# EEZ_DIB_DCM220_r2B8.net
KiCad netlist of a schematic drawn in EAGLE
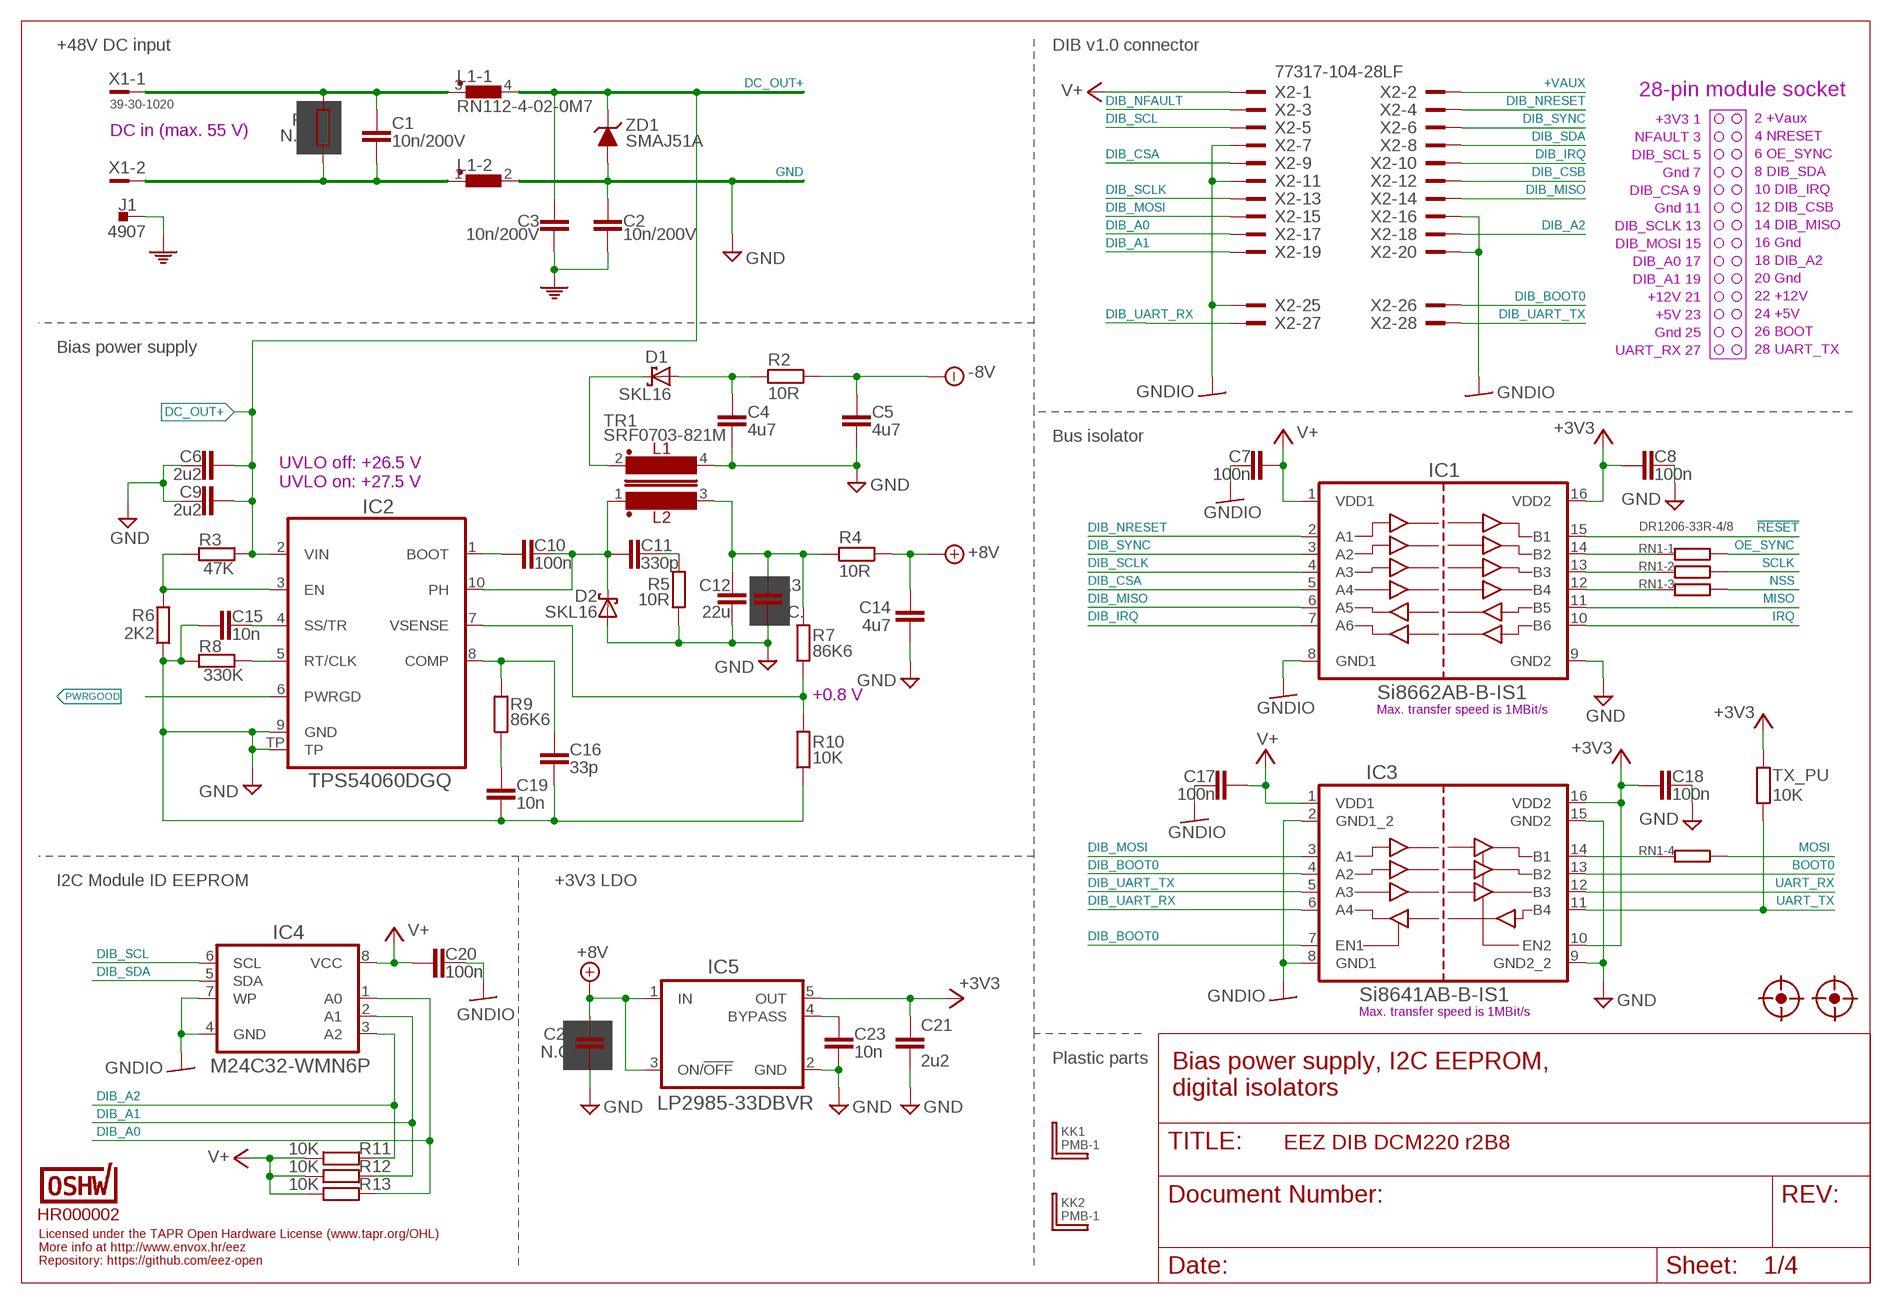
[diagram p0: schematic, sheet 1]
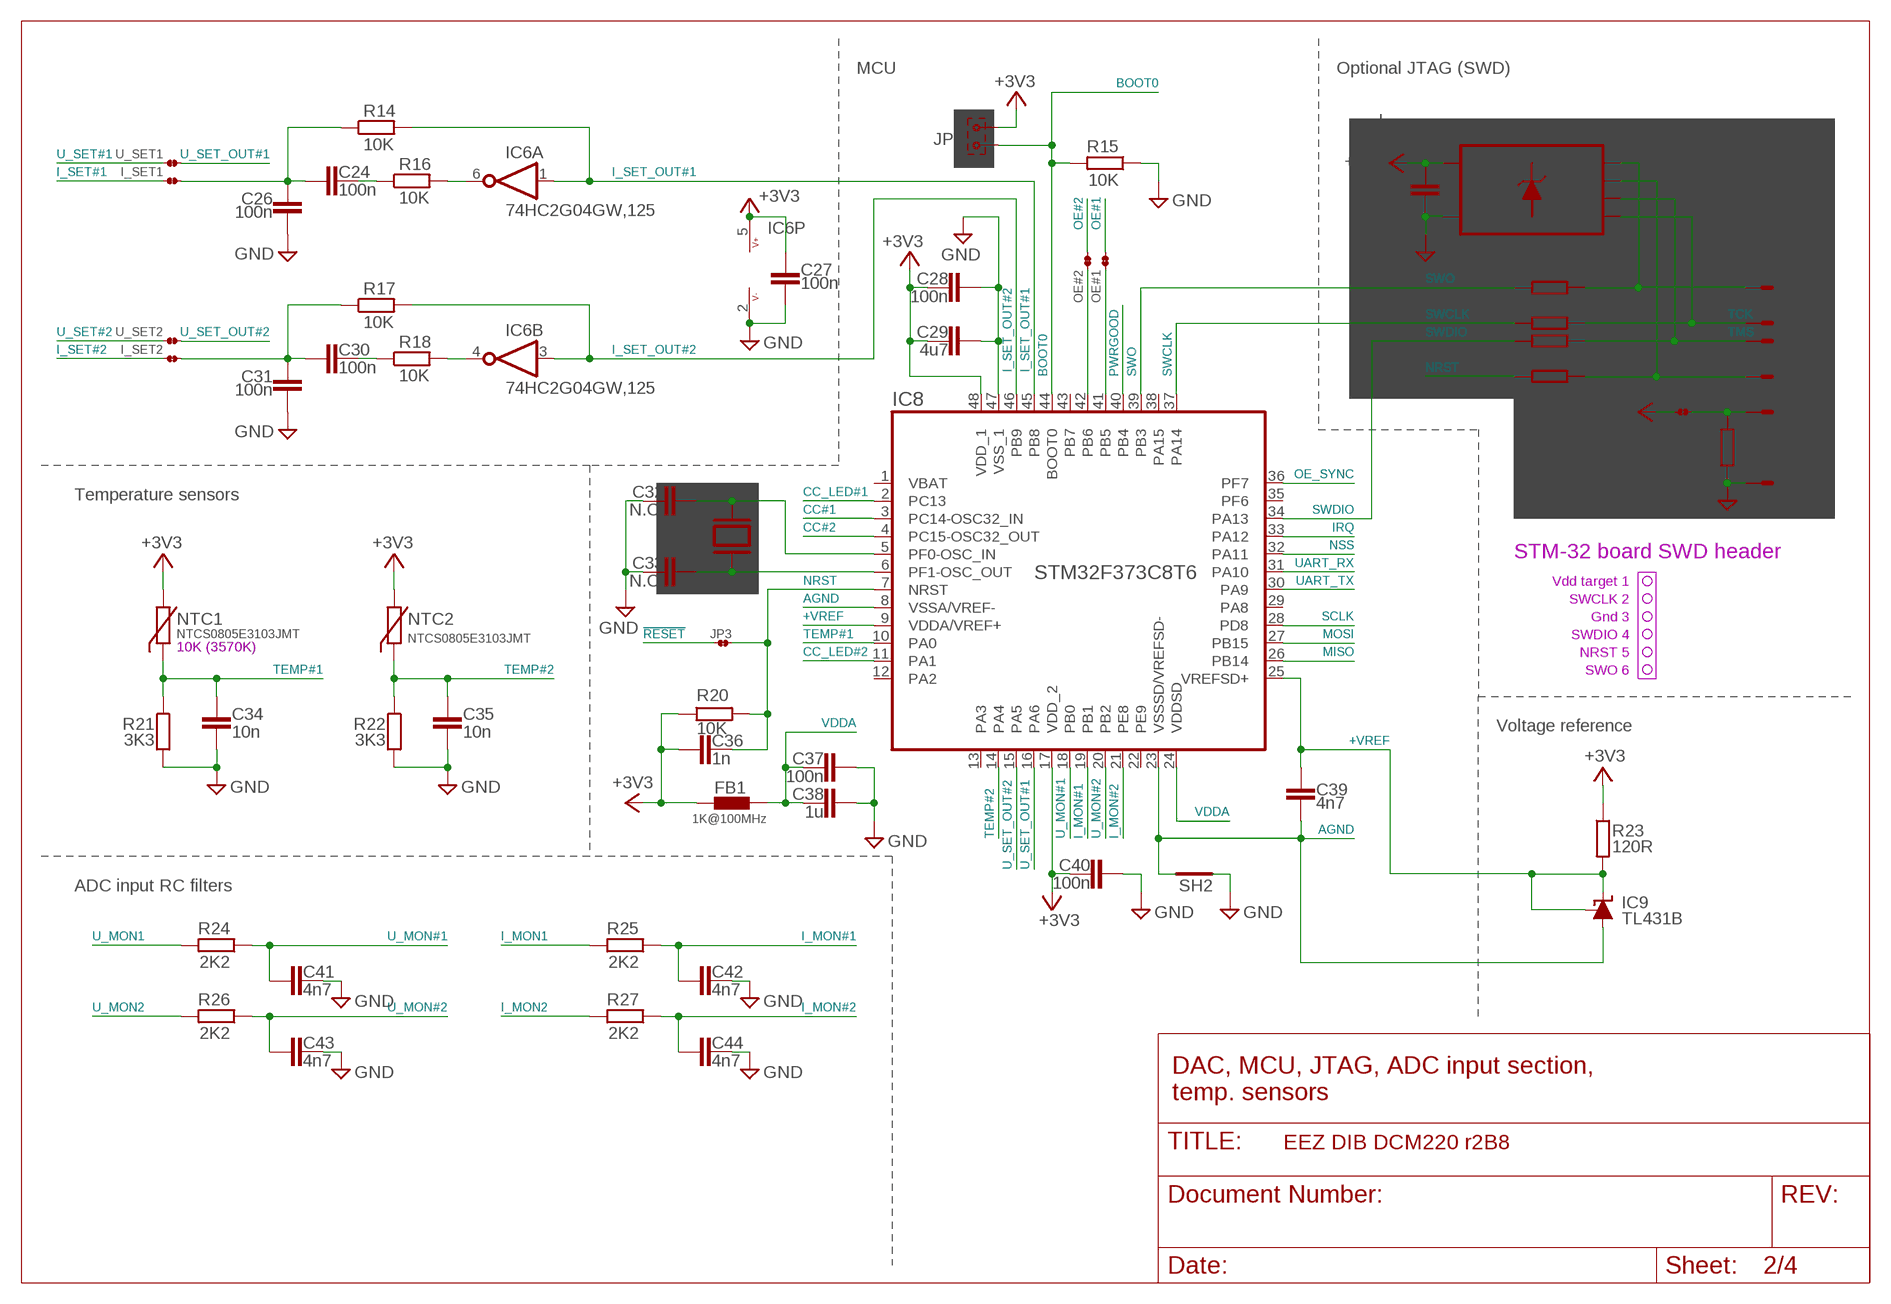
[diagram p1: schematic, sheet 2]
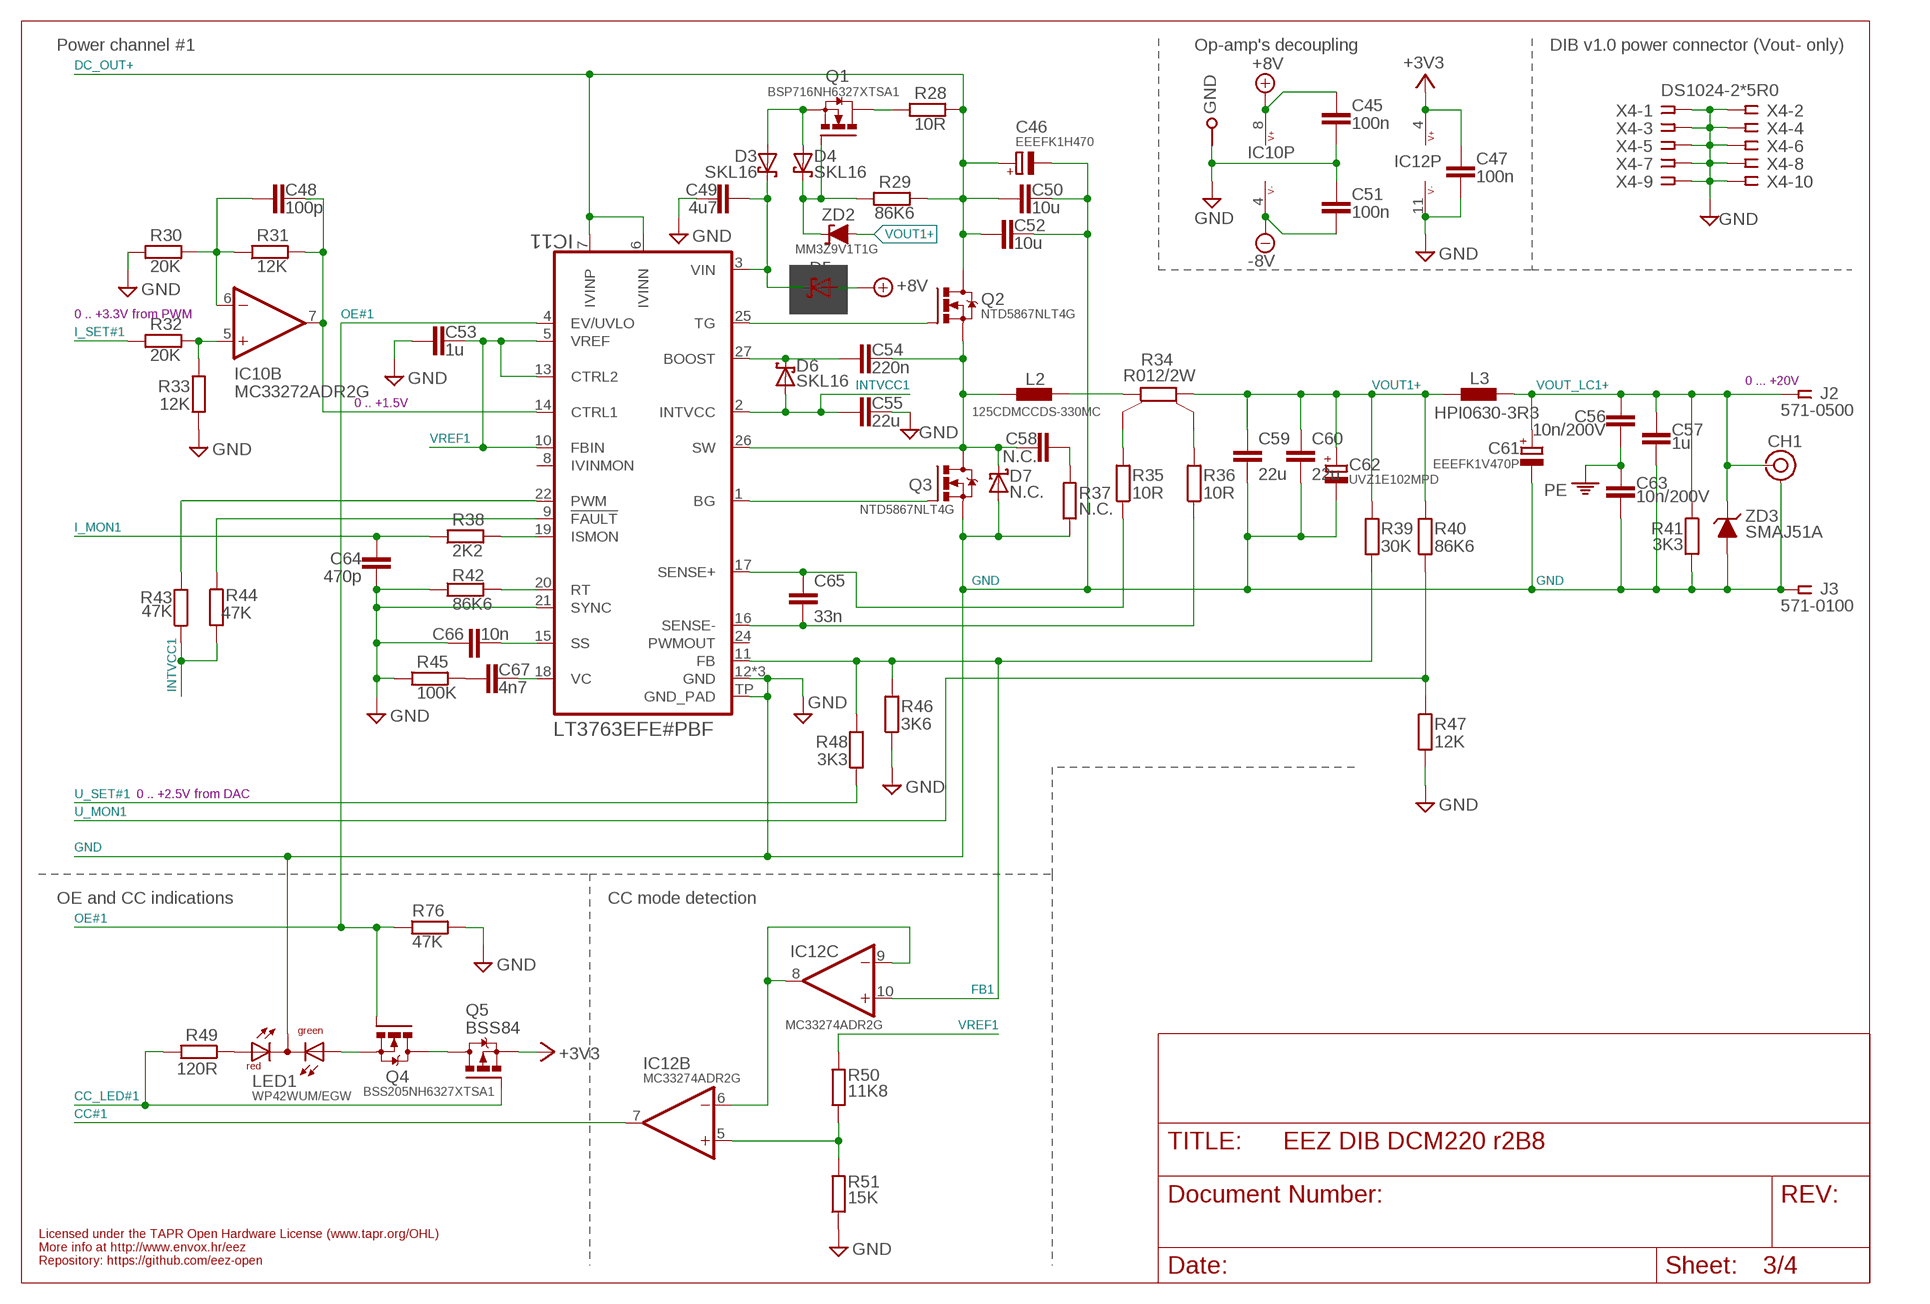
[diagram p2: schematic, sheet 3]
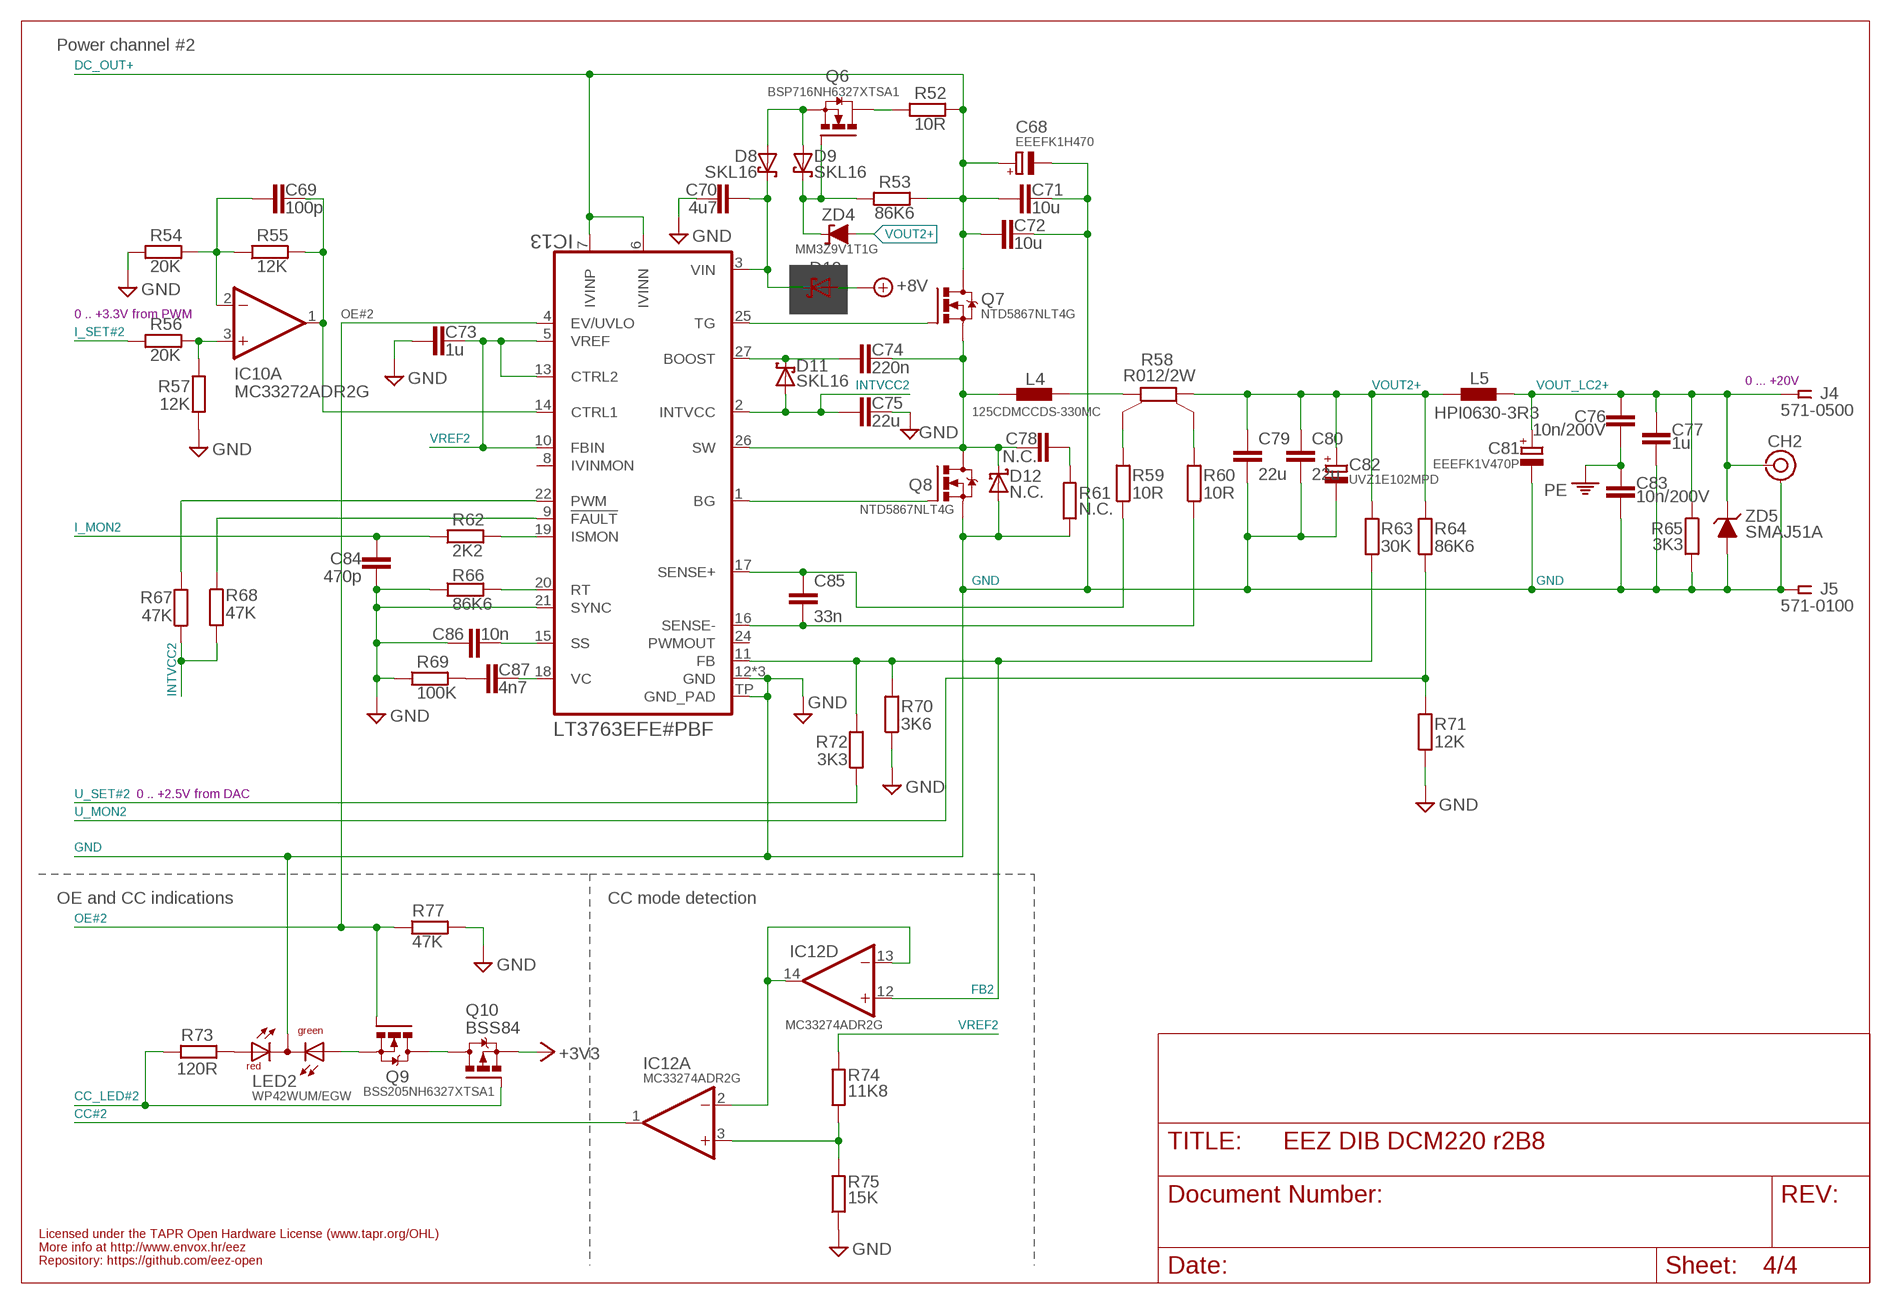
[diagram p3: schematic, sheet 4]

(export (version "E")
  (design (tool "Eeschema 10.0.6"))
  (components
    (comp (ref "C24")
      (value "100n")
      (footprint "eagle-import:C0603")
      (libsource (lib "eagle-import") (part "C-EUC0603"))
    )
    (comp (ref "C25")
      (value "N.C.")
      (footprint "eagle-import:C0603")
      (libsource (lib "eagle-import") (part "C-EUC0603"))
    )
    (comp (ref "C26")
      (value "100n")
      (footprint "eagle-import:C0603")
      (libsource (lib "eagle-import") (part "C-EUC0603"))
    )
    (comp (ref "C27")
      (value "100n")
      (footprint "eagle-import:C0603")
      (libsource (lib "eagle-import") (part "C-EUC0603"))
    )
    (comp (ref "C28")
      (value "100n")
      (footprint "eagle-import:C0603")
      (libsource (lib "eagle-import") (part "C-EUC0603"))
    )
    (comp (ref "C29")
      (value "4u7")
      (footprint "eagle-import:C1206")
      (libsource (lib "eagle-import") (part "C-EUC1206"))
    )
    (comp (ref "C30")
      (value "100n")
      (footprint "eagle-import:C0603")
      (libsource (lib "eagle-import") (part "C-EUC0603"))
    )
    (comp (ref "C31")
      (value "100n")
      (footprint "eagle-import:C0603")
      (libsource (lib "eagle-import") (part "C-EUC0603"))
    )
    (comp (ref "C32")
      (value "N.C.")
      (footprint "eagle-import:C0603")
      (libsource (lib "eagle-import") (part "C-EUC0603"))
    )
    (comp (ref "C33")
      (value "N.C.")
      (footprint "eagle-import:C0603")
      (libsource (lib "eagle-import") (part "C-EUC0603"))
    )
    (comp (ref "C34")
      (value "10n")
      (footprint "eagle-import:C0805")
      (libsource (lib "eagle-import") (part "C-EUC0805"))
    )
    (comp (ref "C35")
      (value "10n")
      (footprint "eagle-import:C0805")
      (libsource (lib "eagle-import") (part "C-EUC0805"))
    )
    (comp (ref "C36")
      (value "1n")
      (footprint "eagle-import:C0805")
      (libsource (lib "eagle-import") (part "C-EUC0805"))
    )
    (comp (ref "C37")
      (value "100n")
      (footprint "eagle-import:C0603")
      (libsource (lib "eagle-import") (part "C-EUC0603"))
    )
    (comp (ref "C38")
      (value "1u")
      (footprint "eagle-import:C0805")
      (libsource (lib "eagle-import") (part "C-EUC0805"))
    )
    (comp (ref "C39")
      (value "4n7")
      (footprint "eagle-import:C0805")
      (libsource (lib "eagle-import") (part "C-EUC0805"))
    )
    (comp (ref "C40")
      (value "100n")
      (footprint "eagle-import:C0603")
      (libsource (lib "eagle-import") (part "C-EUC0603"))
    )
    (comp (ref "C41")
      (value "4n7")
      (footprint "eagle-import:C0805")
      (libsource (lib "eagle-import") (part "C-EUC0805"))
    )
    (comp (ref "C42")
      (value "4n7")
      (footprint "eagle-import:C0805")
      (libsource (lib "eagle-import") (part "C-EUC0805"))
    )
    (comp (ref "C43")
      (value "4n7")
      (footprint "eagle-import:C0805")
      (libsource (lib "eagle-import") (part "C-EUC0805"))
    )
    (comp (ref "C44")
      (value "4n7")
      (footprint "eagle-import:C0805")
      (libsource (lib "eagle-import") (part "C-EUC0805"))
    )
    (comp (ref "FB1")
      (value "1K@100MHz")
      (footprint "eagle-import:BEAD0603")
      (libsource (lib "eagle-import") (part "FERRITE_BEAD0603"))
    )
    (comp (ref "IC6")
      (value "74HC2G04GW,125")
      (footprint "eagle-import:SOT65P210X110-6N")
      (libsource (lib "eagle-import") (part "74HC2G04"))
    )
    (comp (ref "IC7")
      (value "N.C.")
      (footprint "eagle-import:DRL6")
      (libsource (lib "eagle-import") (part "TPD4E001-DRL"))
    )
    (comp (ref "IC8")
      (value "STM32F373C8T6")
      (footprint "eagle-import:LQFP-48")
      (libsource (lib "eagle-import") (part "STM32F373C8T6"))
    )
    (comp (ref "IC9")
      (value "TL431B")
      (footprint "eagle-import:SOT103P240X110-3N")
      (libsource (lib "eagle-import") (part "TL431"))
    )
    (comp (ref "I_SET1")
      (value "JP2-NOCUT")
      (footprint "eagle-import:JP2-NOCUT")
      (libsource (lib "eagle-import") (part "JP2-NOCUT"))
    )
    (comp (ref "I_SET2")
      (value "JP2-NOCUT")
      (footprint "eagle-import:JP2-NOCUT")
      (libsource (lib "eagle-import") (part "JP2-NOCUT"))
    )
    (comp (ref "JP1")
      (value "JUMPER-2PIN-2MM")
      (footprint "eagle-import:2MM-2")
      (libsource (lib "eagle-import") (part "JUMPER-2PIN-2MM"))
    )
    (comp (ref "JP2")
      (value "JP2-CUT")
      (footprint "eagle-import:JP2-CUT")
      (libsource (lib "eagle-import") (part "JP2-CUT"))
    )
    (comp (ref "JP3")
      (value "JP2-NOCUT")
      (footprint "eagle-import:JP2-NOCUT")
      (libsource (lib "eagle-import") (part "JP2-NOCUT"))
    )
    (comp (ref "NTC1")
      (value "NTCS0805E3103JMT")
      (footprint "eagle-import:R_0805")
      (libsource (lib "eagle-import") (part "NTCR_0805"))
    )
    (comp (ref "NTC2")
      (value "NTCS0805E3103JMT")
      (footprint "eagle-import:R_0805")
      (libsource (lib "eagle-import") (part "NTCR_0805"))
    )
    (comp (ref "OE#1")
      (value "JP2-NOCUT")
      (footprint "eagle-import:JP2-NOCUT")
      (libsource (lib "eagle-import") (part "JP2-NOCUT"))
    )
    (comp (ref "OE#2")
      (value "JP2-NOCUT")
      (footprint "eagle-import:JP2-NOCUT")
      (libsource (lib "eagle-import") (part "JP2-NOCUT"))
    )
    (comp (ref "R14")
      (value "10K")
      (footprint "eagle-import:R0805")
      (libsource (lib "eagle-import") (part "R-EU_R0805"))
    )
    (comp (ref "R15")
      (value "10K")
      (footprint "eagle-import:R0805")
      (libsource (lib "eagle-import") (part "R-EU_R0805"))
    )
    (comp (ref "R16")
      (value "10K")
      (footprint "eagle-import:R0805")
      (libsource (lib "eagle-import") (part "R-EU_R0805"))
    )
    (comp (ref "R17")
      (value "10K")
      (footprint "eagle-import:R0805")
      (libsource (lib "eagle-import") (part "R-EU_R0805"))
    )
    (comp (ref "R18")
      (value "10K")
      (footprint "eagle-import:R0805")
      (libsource (lib "eagle-import") (part "R-EU_R0805"))
    )
    (comp (ref "R19")
      (value "N.C.")
      (footprint "eagle-import:R0805")
      (libsource (lib "eagle-import") (part "R-EU_R0805"))
    )
    (comp (ref "R20")
      (value "10K")
      (footprint "eagle-import:R0805")
      (libsource (lib "eagle-import") (part "R-EU_R0805"))
    )
    (comp (ref "R21")
      (value "3K3")
      (footprint "eagle-import:R0805")
      (libsource (lib "eagle-import") (part "R-EU_R0805"))
    )
    (comp (ref "R22")
      (value "3K3")
      (footprint "eagle-import:R0805")
      (libsource (lib "eagle-import") (part "R-EU_R0805"))
    )
    (comp (ref "R23")
      (value "120R")
      (footprint "eagle-import:R0805")
      (libsource (lib "eagle-import") (part "R-EU_R0805"))
    )
    (comp (ref "R24")
      (value "2K2")
      (footprint "eagle-import:R0805")
      (libsource (lib "eagle-import") (part "R-EU_R0805"))
    )
    (comp (ref "R25")
      (value "2K2")
      (footprint "eagle-import:R0805")
      (libsource (lib "eagle-import") (part "R-EU_R0805"))
    )
    (comp (ref "R26")
      (value "2K2")
      (footprint "eagle-import:R0805")
      (libsource (lib "eagle-import") (part "R-EU_R0805"))
    )
    (comp (ref "R27")
      (value "2K2")
      (footprint "eagle-import:R0805")
      (libsource (lib "eagle-import") (part "R-EU_R0805"))
    )
    (comp (ref "RN2")
      (value "N.C.")
      (footprint "eagle-import:CAY16")
      (libsource (lib "eagle-import") (part "R_ARRAY4"))
    )
    (comp (ref "SH2")
      (value "SHORTNOHOLE")
      (footprint "eagle-import:SHORT_NOHOLE")
      (libsource (lib "eagle-import") (part "SHORTNOHOLE"))
    )
    (comp (ref "U_SET1")
      (value "JP2-NOCUT")
      (footprint "eagle-import:JP2-NOCUT")
      (libsource (lib "eagle-import") (part "JP2-NOCUT"))
    )
    (comp (ref "U_SET2")
      (value "JP2-NOCUT")
      (footprint "eagle-import:JP2-NOCUT")
      (libsource (lib "eagle-import") (part "JP2-NOCUT"))
    )
    (comp (ref "X3")
      (value "N.C.")
      (footprint "eagle-import:22-23-2061")
      (fields (field (name "MF") "MOLEX") (field (name "MPN") "22-23-2061"))
      (libsource (lib "eagle-import") (part "22-23-2061"))
    )
    (comp (ref "Y1")
      (value "N.C.")
      (footprint "eagle-import:12SMX(B)")
      (libsource (lib "eagle-import") (part "XTAL7.5X5.1-B"))
    )
    (comp (ref "C1")
      (value "10n/200V")
      (footprint "eagle-import:C1206")
      (libsource (lib "eagle-import") (part "C-EUC1206"))
    )
    (comp (ref "C2")
      (value "10n/200V")
      (footprint "eagle-import:C1206")
      (libsource (lib "eagle-import") (part "C-EUC1206"))
    )
    (comp (ref "C3")
      (value "10n/200V")
      (footprint "eagle-import:C1206")
      (libsource (lib "eagle-import") (part "C-EUC1206"))
    )
    (comp (ref "C4")
      (value "4u7")
      (footprint "eagle-import:C1206")
      (libsource (lib "eagle-import") (part "C-EUC1206"))
    )
    (comp (ref "C5")
      (value "4u7")
      (footprint "eagle-import:C1206")
      (libsource (lib "eagle-import") (part "C-EUC1206"))
    )
    (comp (ref "C6")
      (value "2u2")
      (footprint "eagle-import:C1206")
      (libsource (lib "eagle-import") (part "C-EUC1206"))
    )
    (comp (ref "C7")
      (value "100n")
      (footprint "eagle-import:C0603")
      (libsource (lib "eagle-import") (part "C-EUC0603"))
    )
    (comp (ref "C8")
      (value "100n")
      (footprint "eagle-import:C0603")
      (libsource (lib "eagle-import") (part "C-EUC0603"))
    )
    (comp (ref "C9")
      (value "2u2")
      (footprint "eagle-import:C1206")
      (libsource (lib "eagle-import") (part "C-EUC1206"))
    )
    (comp (ref "C10")
      (value "100n")
      (footprint "eagle-import:C0603")
      (libsource (lib "eagle-import") (part "C-EUC0603"))
    )
    (comp (ref "C11")
      (value "330p")
      (footprint "eagle-import:C0805")
      (libsource (lib "eagle-import") (part "C-EUC0805"))
    )
    (comp (ref "C12")
      (value "22u")
      (footprint "eagle-import:C1206")
      (libsource (lib "eagle-import") (part "C-EUC1206"))
    )
    (comp (ref "C13")
      (value "N.C.")
      (footprint "eagle-import:C1206")
      (libsource (lib "eagle-import") (part "C-EUC1206"))
    )
    (comp (ref "C14")
      (value "4u7")
      (footprint "eagle-import:C1206")
      (libsource (lib "eagle-import") (part "C-EUC1206"))
    )
    (comp (ref "C15")
      (value "10n")
      (footprint "eagle-import:C0805")
      (libsource (lib "eagle-import") (part "C-EUC0805"))
    )
    (comp (ref "C16")
      (value "33p")
      (footprint "eagle-import:C0603")
      (libsource (lib "eagle-import") (part "C-EUC0603"))
    )
    (comp (ref "C17")
      (value "100n")
      (footprint "eagle-import:C0603")
      (libsource (lib "eagle-import") (part "C-EUC0603"))
    )
    (comp (ref "C18")
      (value "100n")
      (footprint "eagle-import:C0603")
      (libsource (lib "eagle-import") (part "C-EUC0603"))
    )
    (comp (ref "C19")
      (value "10n")
      (footprint "eagle-import:C0805")
      (libsource (lib "eagle-import") (part "C-EUC0805"))
    )
    (comp (ref "C20")
      (value "100n")
      (footprint "eagle-import:C0603")
      (libsource (lib "eagle-import") (part "C-EUC0603"))
    )
    (comp (ref "C21")
      (value "2u2")
      (footprint "eagle-import:C1206")
      (libsource (lib "eagle-import") (part "C-EUC1206"))
    )
    (comp (ref "C22")
      (value "N.C.")
      (footprint "eagle-import:C0805")
      (libsource (lib "eagle-import") (part "C-EUC0805"))
    )
    (comp (ref "C23")
      (value "10n")
      (footprint "eagle-import:C0805")
      (libsource (lib "eagle-import") (part "C-EUC0805"))
    )
    (comp (ref "D1")
      (value "SKL16")
      (footprint "eagle-import:SOD123")
      (libsource (lib "eagle-import") (part "SCHOTTKYSOD123"))
    )
    (comp (ref "D2")
      (value "SKL16")
      (footprint "eagle-import:SOD123")
      (libsource (lib "eagle-import") (part "SCHOTTKYSOD123"))
    )
    (comp (ref "FM1")
      (value "FIDUCIAL_2")
      (footprint "eagle-import:FIDUCIAL_DUAL")
      (libsource (lib "eagle-import") (part "FIDUCIAL_2"))
    )
    (comp (ref "FM2")
      (value "FIDUCIAL_2")
      (footprint "eagle-import:FIDUCIAL_DUAL")
      (libsource (lib "eagle-import") (part "FIDUCIAL_2"))
    )
    (comp (ref "IC1")
      (value "Si8662AB-B-IS1")
      (footprint "eagle-import:SOIC-16")
      (libsource (lib "eagle-import") (part "SI8662NSOIC-16"))
    )
    (comp (ref "IC2")
      (value "TPS54060DGQ")
      (footprint "eagle-import:SOP50P490X110-11N")
      (fields (field (name "MPN") "TPS54060ADGQ"))
      (libsource (lib "eagle-import") (part "TPS54060DGQ"))
    )
    (comp (ref "IC3")
      (value "Si8641AB-B-IS1")
      (footprint "eagle-import:SOIC-16")
      (libsource (lib "eagle-import") (part "SI8641NSOIC-16"))
    )
    (comp (ref "IC4")
      (value "M24C32-WMN6P")
      (footprint "eagle-import:SOIC127P600X173-8N")
      (libsource (lib "eagle-import") (part "AT24CXXSOIC8"))
    )
    (comp (ref "IC5")
      (value "LP2985-33DBVR")
      (footprint "eagle-import:SOT95P270X145-5N")
      (libsource (lib "eagle-import") (part "LP2985"))
    )
    (comp (ref "J1")
      (value "4907")
      (footprint "eagle-import:PCB_TAB-4907")
      (libsource (lib "eagle-import") (part "PCB_TAB-4907"))
    )
    (comp (ref "KK1")
      (value "PMB-1")
      (footprint "eagle-import:PCB-MB")
      (libsource (lib "eagle-import") (part "PCB-MB"))
    )
    (comp (ref "KK2")
      (value "PMB-1")
      (footprint "eagle-import:PCB-MB")
      (libsource (lib "eagle-import") (part "PCB-MB"))
    )
    (comp (ref "L1")
      (value "RN112-4-02-0M7")
      (footprint "eagle-import:RN112")
      (libsource (lib "eagle-import") (part "RN112"))
    )
    (comp (ref "R1")
      (value "N.C.")
      (footprint "eagle-import:R2512")
      (libsource (lib "eagle-import") (part "R-EU_R2512"))
    )
    (comp (ref "R2")
      (value "10R")
      (footprint "eagle-import:R0805")
      (libsource (lib "eagle-import") (part "R-EU_R0805"))
    )
    (comp (ref "R3")
      (value "47K")
      (footprint "eagle-import:R0805")
      (libsource (lib "eagle-import") (part "R-EU_R0805"))
    )
    (comp (ref "R4")
      (value "10R")
      (footprint "eagle-import:R0805")
      (libsource (lib "eagle-import") (part "R-EU_R0805"))
    )
    (comp (ref "R5")
      (value "10R")
      (footprint "eagle-import:R0805")
      (libsource (lib "eagle-import") (part "R-EU_R0805"))
    )
    (comp (ref "R6")
      (value "2K2")
      (footprint "eagle-import:R0805")
      (libsource (lib "eagle-import") (part "R-EU_R0805"))
    )
    (comp (ref "R7")
      (value "86K6")
      (footprint "eagle-import:R0805")
      (libsource (lib "eagle-import") (part "R-EU_R0805"))
    )
    (comp (ref "R8")
      (value "330K")
      (footprint "eagle-import:R0805")
      (libsource (lib "eagle-import") (part "R-EU_R0805"))
    )
    (comp (ref "R9")
      (value "86K6")
      (footprint "eagle-import:R0805")
      (libsource (lib "eagle-import") (part "R-EU_R0805"))
    )
    (comp (ref "R10")
      (value "10K")
      (footprint "eagle-import:R0805")
      (libsource (lib "eagle-import") (part "R-EU_R0805"))
    )
    (comp (ref "R11")
      (value "10K")
      (footprint "eagle-import:R0805")
      (libsource (lib "eagle-import") (part "R-EU_R0805"))
    )
    (comp (ref "R12")
      (value "10K")
      (footprint "eagle-import:R0805")
      (libsource (lib "eagle-import") (part "R-EU_R0805"))
    )
    (comp (ref "R13")
      (value "10K")
      (footprint "eagle-import:R0805")
      (libsource (lib "eagle-import") (part "R-EU_R0805"))
    )
    (comp (ref "RN1")
      (value "DR1206-33R-4/8")
      (footprint "eagle-import:CAY16")
      (libsource (lib "eagle-import") (part "R_ARRAY4"))
    )
    (comp (ref "TR1")
      (value "SRF0703-821M")
      (footprint "eagle-import:SRF0703")
      (libsource (lib "eagle-import") (part "BOURNS_SRF0703INV"))
    )
    (comp (ref "TX_PU")
      (value "10K")
      (footprint "eagle-import:R0805")
      (libsource (lib "eagle-import") (part "R-EU_R0805"))
    )
    (comp (ref "U$3")
      (value "HR000002")
      (footprint "eagle-import:CERT-SMALL-SILK")
      (libsource (lib "eagle-import") (part "CERT-SMALL"))
    )
    (comp (ref "X1")
      (value "39-30-1020")
      (footprint "eagle-import:MINIFIT_39301020")
      (libsource (lib "eagle-import") (part "MINIFIT_39301020"))
    )
    (comp (ref "X2")
      (value "77317-104-28LF")
      (footprint "eagle-import:77317-104-28LF")
      (libsource (lib "eagle-import") (part "77317-104-28LF"))
    )
    (comp (ref "ZD1")
      (value "SMAJ51A")
      (footprint "eagle-import:DO214AA")
      (libsource (lib "eagle-import") (part "P6SMB68A"))
    )
    (comp (ref "C68")
      (value "EEEFK1H470")
      (footprint "eagle-import:CAPAE830X1050N")
      (libsource (lib "eagle-import") (part "ECAPSMD8.3MM/HA0"))
    )
    (comp (ref "C69")
      (value "100p")
      (footprint "eagle-import:C0805")
      (libsource (lib "eagle-import") (part "C-EUC0805"))
    )
    (comp (ref "C70")
      (value "4u7")
      (footprint "eagle-import:C1206")
      (libsource (lib "eagle-import") (part "C-EUC1206"))
    )
    (comp (ref "C71")
      (value "10u")
      (footprint "eagle-import:C1210")
      (libsource (lib "eagle-import") (part "C-EUC1210"))
    )
    (comp (ref "C72")
      (value "10u")
      (footprint "eagle-import:C1210")
      (libsource (lib "eagle-import") (part "C-EUC1210"))
    )
    (comp (ref "C73")
      (value "1u")
      (footprint "eagle-import:C0805")
      (libsource (lib "eagle-import") (part "C-EUC0805"))
    )
    (comp (ref "C74")
      (value "220n")
      (footprint "eagle-import:C0805")
      (libsource (lib "eagle-import") (part "C-EUC0805"))
    )
    (comp (ref "C75")
      (value "22u")
      (footprint "eagle-import:C1206")
      (libsource (lib "eagle-import") (part "C-EUC1206"))
    )
    (comp (ref "C76")
      (value "10n/200V")
      (footprint "eagle-import:C1206")
      (libsource (lib "eagle-import") (part "C-EUC1206"))
    )
    (comp (ref "C77")
      (value "1u")
      (footprint "eagle-import:C0805")
      (libsource (lib "eagle-import") (part "C-EUC0805"))
    )
    (comp (ref "C78")
      (value "N.C.")
      (footprint "eagle-import:C0805")
      (libsource (lib "eagle-import") (part "C-EUC0805"))
    )
    (comp (ref "C79")
      (value "22u")
      (footprint "eagle-import:C1210")
      (libsource (lib "eagle-import") (part "C-EUC1210"))
    )
    (comp (ref "C80")
      (value "22u")
      (footprint "eagle-import:C1210")
      (libsource (lib "eagle-import") (part "C-EUC1210"))
    )
    (comp (ref "C81")
      (value "EEEFK1V470P")
      (footprint "eagle-import:CAPAE660X610N")
      (libsource (lib "eagle-import") (part "ECAPPANASONIC_H"))
    )
    (comp (ref "C82")
      (value "UVZ1E102MPD")
      (footprint "eagle-import:ECAP5_10.5")
      (libsource (lib "eagle-import") (part "ECAP5G_10.5MM"))
    )
    (comp (ref "C83")
      (value "10n/200V")
      (footprint "eagle-import:C1206")
      (libsource (lib "eagle-import") (part "C-EUC1206"))
    )
    (comp (ref "C84")
      (value "470p")
      (footprint "eagle-import:C0805")
      (libsource (lib "eagle-import") (part "C-EUC0805"))
    )
    (comp (ref "C85")
      (value "33n")
      (footprint "eagle-import:C0805")
      (libsource (lib "eagle-import") (part "C-EUC0805"))
    )
    (comp (ref "C86")
      (value "10n")
      (footprint "eagle-import:C0805")
      (libsource (lib "eagle-import") (part "C-EUC0805"))
    )
    (comp (ref "C87")
      (value "4n7")
      (footprint "eagle-import:C0805")
      (libsource (lib "eagle-import") (part "C-EUC0805"))
    )
    (comp (ref "CH2")
      (value "TEST_POINT-2")
      (footprint "eagle-import:TP_1.1MM_2")
      (libsource (lib "eagle-import") (part "TEST_POINT-2"))
    )
    (comp (ref "D8")
      (value "SKL16")
      (footprint "eagle-import:SOD123")
      (libsource (lib "eagle-import") (part "SCHOTTKYSOD123"))
    )
    (comp (ref "D9")
      (value "SKL16")
      (footprint "eagle-import:SOD123")
      (libsource (lib "eagle-import") (part "SCHOTTKYSOD123"))
    )
    (comp (ref "D10")
      (value "N.C.")
      (footprint "eagle-import:SOD123")
      (libsource (lib "eagle-import") (part "SCHOTTKYSOD123"))
    )
    (comp (ref "D11")
      (value "SKL16")
      (footprint "eagle-import:SOD123")
      (libsource (lib "eagle-import") (part "SCHOTTKYSOD123"))
    )
    (comp (ref "D12")
      (value "N.C.")
      (footprint "eagle-import:SMA")
      (libsource (lib "eagle-import") (part "SCHOTTKYSMA_DO-214AC"))
    )
    (comp (ref "IC10")
      (value "MC33272ADR2G")
      (footprint "eagle-import:SOIC127P600X173-8N")
      (libsource (lib "eagle-import") (part "TL072SOIC8"))
    )
    (comp (ref "IC12")
      (value "MC33274ADR2G")
      (footprint "eagle-import:SOIC127P600X175-14N")
      (fields (field (name "MPN") "TL074ACD"))
      (libsource (lib "eagle-import") (part "TL074SOIC14"))
    )
    (comp (ref "IC13")
      (value "LT3763EFE#PBF")
      (footprint "eagle-import:LTC_05-08-1663-EB")
      (libsource (lib "eagle-import") (part "LT3763EFE#PBF"))
    )
    (comp (ref "J4")
      (value "571-0500")
      (footprint "eagle-import:DELTRON_571")
      (libsource (lib "eagle-import") (part "571-0500"))
    )
    (comp (ref "J5")
      (value "571-0100")
      (footprint "eagle-import:DELTRON_571")
      (libsource (lib "eagle-import") (part "571-0100"))
    )
    (comp (ref "L4")
      (value "125CDMCCDS-330MC")
      (footprint "eagle-import:125CDMCC_DS")
      (libsource (lib "eagle-import") (part "125CDMCC/DS"))
    )
    (comp (ref "L5")
      (value "HPI0630-3R3")
      (footprint "eagle-import:COILCRAFT_HPI0630")
      (libsource (lib "eagle-import") (part "COILCRAFT_HPI0630"))
    )
    (comp (ref "LED2")
      (value "WP42WUM/EGW")
      (footprint "eagle-import:L-42WUM-1EGWT")
      (libsource (lib "eagle-import") (part "LED_L-42WUM/1EGWT"))
    )
    (comp (ref "Q6")
      (value "BSP716NH6327XTSA1")
      (footprint "eagle-import:SOT223")
      (libsource (lib "eagle-import") (part "N-HEXFET-2D_?-SOT232IRLL014N"))
    )
    (comp (ref "Q7")
      (value "NTD5867NLT4G")
      (footprint "eagle-import:TO229P990X239-3N")
      (libsource (lib "eagle-import") (part "N-MOSFETDPAK"))
    )
    (comp (ref "Q8")
      (value "NTD5867NLT4G")
      (footprint "eagle-import:TO229P990X239-3N")
      (libsource (lib "eagle-import") (part "N-MOSFETDPAK"))
    )
    (comp (ref "Q9")
      (value "BSS205NH6327XTSA1")
      (footprint "eagle-import:SOT103P240X110-3N")
      (fields (field (name "MPN") "2N7002-7-F"))
      (libsource (lib "eagle-import") (part "2N7002"))
    )
    (comp (ref "Q10")
      (value "BSS84")
      (footprint "eagle-import:SOT95P237X112-3N")
      (fields (field (name "MPN") "IRLML2246TRPBF"))
      (libsource (lib "eagle-import") (part "IRLML2246TRPBF"))
    )
    (comp (ref "R52")
      (value "10R")
      (footprint "eagle-import:R0805")
      (libsource (lib "eagle-import") (part "R-EU_R0805"))
    )
    (comp (ref "R53")
      (value "86K6")
      (footprint "eagle-import:R0805")
      (libsource (lib "eagle-import") (part "R-EU_R0805"))
    )
    (comp (ref "R54")
      (value "20K")
      (footprint "eagle-import:R0805")
      (libsource (lib "eagle-import") (part "R-EU_R0805"))
    )
    (comp (ref "R55")
      (value "12K")
      (footprint "eagle-import:R0805")
      (libsource (lib "eagle-import") (part "R-EU_R0805"))
    )
    (comp (ref "R56")
      (value "20K")
      (footprint "eagle-import:R0805")
      (libsource (lib "eagle-import") (part "R-EU_R0805"))
    )
    (comp (ref "R57")
      (value "12K")
      (footprint "eagle-import:R0805")
      (libsource (lib "eagle-import") (part "R-EU_R0805"))
    )
    (comp (ref "R58")
      (value "R012/2W")
      (footprint "eagle-import:R_2512-4WIRE")
      (libsource (lib "eagle-import") (part "R-EU_4WIRE2512"))
    )
    (comp (ref "R59")
      (value "10R")
      (footprint "eagle-import:R0805")
      (libsource (lib "eagle-import") (part "R-EU_R0805"))
    )
    (comp (ref "R60")
      (value "10R")
      (footprint "eagle-import:R0805")
      (libsource (lib "eagle-import") (part "R-EU_R0805"))
    )
    (comp (ref "R61")
      (value "N.C.")
      (footprint "eagle-import:R1206")
      (libsource (lib "eagle-import") (part "R-EU_R1206"))
    )
    (comp (ref "R62")
      (value "2K2")
      (footprint "eagle-import:R0805")
      (libsource (lib "eagle-import") (part "R-EU_R0805"))
    )
    (comp (ref "R63")
      (value "30K")
      (footprint "eagle-import:R0805")
      (libsource (lib "eagle-import") (part "R-EU_R0805"))
    )
    (comp (ref "R64")
      (value "86K6")
      (footprint "eagle-import:R0805")
      (libsource (lib "eagle-import") (part "R-EU_R0805"))
    )
    (comp (ref "R65")
      (value "3K3")
      (footprint "eagle-import:R0805")
      (libsource (lib "eagle-import") (part "R-EU_R0805"))
    )
    (comp (ref "R66")
      (value "86K6")
      (footprint "eagle-import:R0805")
      (libsource (lib "eagle-import") (part "R-EU_R0805"))
    )
    (comp (ref "R67")
      (value "47K")
      (footprint "eagle-import:R0805")
      (libsource (lib "eagle-import") (part "R-EU_R0805"))
    )
    (comp (ref "R68")
      (value "47K")
      (footprint "eagle-import:R0805")
      (libsource (lib "eagle-import") (part "R-EU_R0805"))
    )
    (comp (ref "R69")
      (value "100K")
      (footprint "eagle-import:R0805")
      (libsource (lib "eagle-import") (part "R-EU_R0805"))
    )
    (comp (ref "R70")
      (value "3K6")
      (footprint "eagle-import:R0805")
      (libsource (lib "eagle-import") (part "R-EU_R0805"))
    )
    (comp (ref "R71")
      (value "12K")
      (footprint "eagle-import:R0805")
      (libsource (lib "eagle-import") (part "R-EU_R0805"))
    )
    (comp (ref "R72")
      (value "3K3")
      (footprint "eagle-import:R0805")
      (libsource (lib "eagle-import") (part "R-EU_R0805"))
    )
    (comp (ref "R73")
      (value "120R")
      (footprint "eagle-import:R0805")
      (libsource (lib "eagle-import") (part "R-EU_R0805"))
    )
    (comp (ref "R74")
      (value "11K8")
      (footprint "eagle-import:R0805")
      (libsource (lib "eagle-import") (part "R-EU_R0805"))
    )
    (comp (ref "R75")
      (value "15K")
      (footprint "eagle-import:R0805")
      (libsource (lib "eagle-import") (part "R-EU_R0805"))
    )
    (comp (ref "R77")
      (value "47K")
      (footprint "eagle-import:R0805")
      (libsource (lib "eagle-import") (part "R-EU_R0805"))
    )
    (comp (ref "ZD4")
      (value "MM3Z9V1T1G")
      (footprint "eagle-import:SOD323-W")
      (libsource (lib "eagle-import") (part "ZENER-DIODESOD323"))
    )
    (comp (ref "ZD5")
      (value "SMAJ51A")
      (footprint "eagle-import:DO214AA")
      (libsource (lib "eagle-import") (part "P6SMB68A"))
    )
    (comp (ref "C45")
      (value "100n")
      (footprint "eagle-import:C0603")
      (libsource (lib "eagle-import") (part "C-EUC0603"))
    )
    (comp (ref "C46")
      (value "EEEFK1H470")
      (footprint "eagle-import:CAPAE830X1050N")
      (libsource (lib "eagle-import") (part "ECAPSMD8.3MM/HA0"))
    )
    (comp (ref "C47")
      (value "100n")
      (footprint "eagle-import:C0603")
      (libsource (lib "eagle-import") (part "C-EUC0603"))
    )
    (comp (ref "C48")
      (value "100p")
      (footprint "eagle-import:C0805")
      (libsource (lib "eagle-import") (part "C-EUC0805"))
    )
    (comp (ref "C49")
      (value "4u7")
      (footprint "eagle-import:C1206")
      (libsource (lib "eagle-import") (part "C-EUC1206"))
    )
    (comp (ref "C50")
      (value "10u")
      (footprint "eagle-import:C1210")
      (libsource (lib "eagle-import") (part "C-EUC1210"))
    )
    (comp (ref "C51")
      (value "100n")
      (footprint "eagle-import:C0603")
      (libsource (lib "eagle-import") (part "C-EUC0603"))
    )
    (comp (ref "C52")
      (value "10u")
      (footprint "eagle-import:C1210")
      (libsource (lib "eagle-import") (part "C-EUC1210"))
    )
    (comp (ref "C53")
      (value "1u")
      (footprint "eagle-import:C0805")
      (libsource (lib "eagle-import") (part "C-EUC0805"))
    )
    (comp (ref "C54")
      (value "220n")
      (footprint "eagle-import:C0805")
      (libsource (lib "eagle-import") (part "C-EUC0805"))
    )
    (comp (ref "C55")
      (value "22u")
      (footprint "eagle-import:C1206")
      (libsource (lib "eagle-import") (part "C-EUC1206"))
    )
    (comp (ref "C56")
      (value "10n/200V")
      (footprint "eagle-import:C1206")
      (libsource (lib "eagle-import") (part "C-EUC1206"))
    )
    (comp (ref "C57")
      (value "1u")
      (footprint "eagle-import:C0805")
      (libsource (lib "eagle-import") (part "C-EUC0805"))
    )
    (comp (ref "C58")
      (value "N.C.")
      (footprint "eagle-import:C0805")
      (libsource (lib "eagle-import") (part "C-EUC0805"))
    )
    (comp (ref "C59")
      (value "22u")
      (footprint "eagle-import:C1210")
      (libsource (lib "eagle-import") (part "C-EUC1210"))
    )
    (comp (ref "C60")
      (value "22u")
      (footprint "eagle-import:C1210")
      (libsource (lib "eagle-import") (part "C-EUC1210"))
    )
    (comp (ref "C61")
      (value "EEEFK1V470P")
      (footprint "eagle-import:CAPAE660X610N")
      (libsource (lib "eagle-import") (part "ECAPPANASONIC_H"))
    )
    (comp (ref "C62")
      (value "UVZ1E102MPD")
      (footprint "eagle-import:ECAP5_10.5")
      (libsource (lib "eagle-import") (part "ECAP5G_10.5MM"))
    )
    (comp (ref "C63")
      (value "10n/200V")
      (footprint "eagle-import:C1206")
      (libsource (lib "eagle-import") (part "C-EUC1206"))
    )
    (comp (ref "C64")
      (value "470p")
      (footprint "eagle-import:C0805")
      (libsource (lib "eagle-import") (part "C-EUC0805"))
    )
    (comp (ref "C65")
      (value "33n")
      (footprint "eagle-import:C0805")
      (libsource (lib "eagle-import") (part "C-EUC0805"))
    )
    (comp (ref "C66")
      (value "10n")
      (footprint "eagle-import:C0805")
      (libsource (lib "eagle-import") (part "C-EUC0805"))
    )
    (comp (ref "C67")
      (value "4n7")
      (footprint "eagle-import:C0805")
      (libsource (lib "eagle-import") (part "C-EUC0805"))
    )
    (comp (ref "CH1")
      (value "TEST_POINT-2")
      (footprint "eagle-import:TP_1.1MM_2")
      (libsource (lib "eagle-import") (part "TEST_POINT-2"))
    )
    (comp (ref "D3")
      (value "SKL16")
      (footprint "eagle-import:SOD123")
      (libsource (lib "eagle-import") (part "SCHOTTKYSOD123"))
    )
    (comp (ref "D4")
      (value "SKL16")
      (footprint "eagle-import:SOD123")
      (libsource (lib "eagle-import") (part "SCHOTTKYSOD123"))
    )
    (comp (ref "D5")
      (value "N.C.")
      (footprint "eagle-import:SOD123")
      (libsource (lib "eagle-import") (part "SCHOTTKYSOD123"))
    )
    (comp (ref "D6")
      (value "SKL16")
      (footprint "eagle-import:SOD123")
      (libsource (lib "eagle-import") (part "SCHOTTKYSOD123"))
    )
    (comp (ref "D7")
      (value "N.C.")
      (footprint "eagle-import:SMA")
      (libsource (lib "eagle-import") (part "SCHOTTKYSMA_DO-214AC"))
    )
    (comp (ref "GND")
      (value "TEST-PIN_0.9MM")
      (footprint "eagle-import:TEST-PIN_0.9MM")
      (libsource (lib "eagle-import") (part "TEST-PIN_0.9MM"))
    )
    (comp (ref "IC11")
      (value "LT3763EFE#PBF")
      (footprint "eagle-import:LTC_05-08-1663-EB")
      (libsource (lib "eagle-import") (part "LT3763EFE#PBF"))
    )
    (comp (ref "J2")
      (value "571-0500")
      (footprint "eagle-import:DELTRON_571")
      (libsource (lib "eagle-import") (part "571-0500"))
    )
    (comp (ref "J3")
      (value "571-0100")
      (footprint "eagle-import:DELTRON_571")
      (libsource (lib "eagle-import") (part "571-0100"))
    )
    (comp (ref "L2")
      (value "125CDMCCDS-330MC")
      (footprint "eagle-import:125CDMCC_DS")
      (libsource (lib "eagle-import") (part "125CDMCC/DS"))
    )
    (comp (ref "L3")
      (value "HPI0630-3R3")
      (footprint "eagle-import:COILCRAFT_HPI0630")
      (libsource (lib "eagle-import") (part "COILCRAFT_HPI0630"))
    )
    (comp (ref "LED1")
      (value "WP42WUM/EGW")
      (footprint "eagle-import:L-42WUM-1EGWT")
      (libsource (lib "eagle-import") (part "LED_L-42WUM/1EGWT"))
    )
    (comp (ref "Q1")
      (value "BSP716NH6327XTSA1")
      (footprint "eagle-import:SOT223")
      (libsource (lib "eagle-import") (part "N-HEXFET-2D_?-SOT232IRLL014N"))
    )
    (comp (ref "Q2")
      (value "NTD5867NLT4G")
      (footprint "eagle-import:TO229P990X239-3N")
      (libsource (lib "eagle-import") (part "N-MOSFETDPAK"))
    )
    (comp (ref "Q3")
      (value "NTD5867NLT4G")
      (footprint "eagle-import:TO229P990X239-3N")
      (libsource (lib "eagle-import") (part "N-MOSFETDPAK"))
    )
    (comp (ref "Q4")
      (value "BSS205NH6327XTSA1")
      (footprint "eagle-import:SOT103P240X110-3N")
      (fields (field (name "MPN") "2N7002-7-F"))
      (libsource (lib "eagle-import") (part "2N7002"))
    )
    (comp (ref "Q5")
      (value "BSS84")
      (footprint "eagle-import:SOT95P237X112-3N")
      (fields (field (name "MPN") "IRLML2246TRPBF"))
      (libsource (lib "eagle-import") (part "IRLML2246TRPBF"))
    )
    (comp (ref "R28")
      (value "10R")
      (footprint "eagle-import:R0805")
      (libsource (lib "eagle-import") (part "R-EU_R0805"))
    )
    (comp (ref "R29")
      (value "86K6")
      (footprint "eagle-import:R0805")
      (libsource (lib "eagle-import") (part "R-EU_R0805"))
    )
    (comp (ref "R30")
      (value "20K")
      (footprint "eagle-import:R0805")
      (libsource (lib "eagle-import") (part "R-EU_R0805"))
    )
    (comp (ref "R31")
      (value "12K")
      (footprint "eagle-import:R0805")
      (libsource (lib "eagle-import") (part "R-EU_R0805"))
    )
    (comp (ref "R32")
      (value "20K")
      (footprint "eagle-import:R0805")
      (libsource (lib "eagle-import") (part "R-EU_R0805"))
    )
    (comp (ref "R33")
      (value "12K")
      (footprint "eagle-import:R0805")
      (libsource (lib "eagle-import") (part "R-EU_R0805"))
    )
    (comp (ref "R34")
      (value "R012/2W")
      (footprint "eagle-import:R_2512-4WIRE")
      (libsource (lib "eagle-import") (part "R-EU_4WIRE2512"))
    )
    (comp (ref "R35")
      (value "10R")
      (footprint "eagle-import:R0805")
      (libsource (lib "eagle-import") (part "R-EU_R0805"))
    )
    (comp (ref "R36")
      (value "10R")
      (footprint "eagle-import:R0805")
      (libsource (lib "eagle-import") (part "R-EU_R0805"))
    )
    (comp (ref "R37")
      (value "N.C.")
      (footprint "eagle-import:R1206")
      (libsource (lib "eagle-import") (part "R-EU_R1206"))
    )
    (comp (ref "R38")
      (value "2K2")
      (footprint "eagle-import:R0805")
      (libsource (lib "eagle-import") (part "R-EU_R0805"))
    )
    (comp (ref "R39")
      (value "30K")
      (footprint "eagle-import:R0805")
      (libsource (lib "eagle-import") (part "R-EU_R0805"))
    )
    (comp (ref "R40")
      (value "86K6")
      (footprint "eagle-import:R0805")
      (libsource (lib "eagle-import") (part "R-EU_R0805"))
    )
    (comp (ref "R41")
      (value "3K3")
      (footprint "eagle-import:R0805")
      (libsource (lib "eagle-import") (part "R-EU_R0805"))
    )
    (comp (ref "R42")
      (value "86K6")
      (footprint "eagle-import:R0805")
      (libsource (lib "eagle-import") (part "R-EU_R0805"))
    )
    (comp (ref "R43")
      (value "47K")
      (footprint "eagle-import:R0805")
      (libsource (lib "eagle-import") (part "R-EU_R0805"))
    )
    (comp (ref "R44")
      (value "47K")
      (footprint "eagle-import:R0805")
      (libsource (lib "eagle-import") (part "R-EU_R0805"))
    )
    (comp (ref "R45")
      (value "100K")
      (footprint "eagle-import:R0805")
      (libsource (lib "eagle-import") (part "R-EU_R0805"))
    )
    (comp (ref "R46")
      (value "3K6")
      (footprint "eagle-import:R0805")
      (libsource (lib "eagle-import") (part "R-EU_R0805"))
    )
    (comp (ref "R47")
      (value "12K")
      (footprint "eagle-import:R0805")
      (libsource (lib "eagle-import") (part "R-EU_R0805"))
    )
    (comp (ref "R48")
      (value "3K3")
      (footprint "eagle-import:R0805")
      (libsource (lib "eagle-import") (part "R-EU_R0805"))
    )
    (comp (ref "R49")
      (value "120R")
      (footprint "eagle-import:R0805")
      (libsource (lib "eagle-import") (part "R-EU_R0805"))
    )
    (comp (ref "R50")
      (value "11K8")
      (footprint "eagle-import:R0805")
      (libsource (lib "eagle-import") (part "R-EU_R0805"))
    )
    (comp (ref "R51")
      (value "15K")
      (footprint "eagle-import:R0805")
      (libsource (lib "eagle-import") (part "R-EU_R0805"))
    )
    (comp (ref "R76")
      (value "47K")
      (footprint "eagle-import:R0805")
      (libsource (lib "eagle-import") (part "R-EU_R0805"))
    )
    (comp (ref "X4")
      (value "DS1024-2*5R0")
      (footprint "eagle-import:SSW-105-02-T-D-RA")
      (libsource (lib "eagle-import") (part "SSW-105-02-T-D-RA"))
    )
    (comp (ref "ZD2")
      (value "MM3Z9V1T1G")
      (footprint "eagle-import:SOD323-W")
      (libsource (lib "eagle-import") (part "ZENER-DIODESOD323"))
    )
    (comp (ref "ZD3")
      (value "SMAJ51A")
      (footprint "eagle-import:DO214AA")
      (libsource (lib "eagle-import") (part "P6SMB68A"))
    )
  )
  (nets
    (net (code "1") (name "+3V3") (class "Default")
      (node (ref "C18") (pin "2") (pinfunction "2_2") (pintype "passive"))
      (node (ref "C21") (pin "1") (pinfunction "1_1") (pintype "passive"))
      (node (ref "C25") (pin "1") (pinfunction "1_1") (pintype "passive"))
      (node (ref "C27") (pin "1") (pinfunction "1_1") (pintype "passive"))
      (node (ref "C28") (pin "2") (pinfunction "2_2") (pintype "passive"))
      (node (ref "C29") (pin "1") (pinfunction "1_1") (pintype "passive"))
      (node (ref "C36") (pin "2") (pinfunction "2_2") (pintype "passive"))
      (node (ref "C40") (pin "2") (pinfunction "2_2") (pintype "passive"))
      (node (ref "C47") (pin "1") (pinfunction "1_1") (pintype "passive"))
      (node (ref "C8") (pin "2") (pinfunction "2_2") (pintype "passive"))
      (node (ref "FB1") (pin "P$1") (pinfunction "1_P$1") (pintype "passive"))
      (node (ref "IC1") (pin "16") (pinfunction "VDD2_16") (pintype "passive"))
      (node (ref "IC12") (pin "4") (pinfunction "V+_4") (pintype "power_in"))
      (node (ref "IC3") (pin "10") (pinfunction "EN2_10") (pintype "input"))
      (node (ref "IC3") (pin "16") (pinfunction "VDD2_16") (pintype "passive"))
      (node (ref "IC5") (pin "5") (pinfunction "OUT_5") (pintype "passive"))
      (node (ref "IC6") (pin "5") (pinfunction "V+_5") (pintype "power_in"))
      (node (ref "IC7") (pin "6") (pinfunction "VCC_6") (pintype "passive"))
      (node (ref "IC8") (pin "17") (pinfunction "VDD_2_17") (pintype "passive"))
      (node (ref "IC8") (pin "48") (pinfunction "VDD_1_48") (pintype "bidirectional"))
      (node (ref "JP1") (pin "1") (pinfunction "1_1") (pintype "passive"))
      (node (ref "JP2") (pin "1") (pinfunction "1_1") (pintype "passive"))
      (node (ref "NTC1") (pin "1") (pinfunction "P$1_1") (pintype "bidirectional"))
      (node (ref "NTC2") (pin "1") (pinfunction "P$1_1") (pintype "bidirectional"))
      (node (ref "Q10") (pin "2") (pinfunction "S_2") (pintype "passive"))
      (node (ref "Q5") (pin "2") (pinfunction "S_2") (pintype "passive"))
      (node (ref "R20") (pin "1") (pinfunction "1_1") (pintype "passive"))
      (node (ref "R23") (pin "1") (pinfunction "1_1") (pintype "passive"))
      (node (ref "TX_PU") (pin "2") (pinfunction "2_2") (pintype "passive"))
    )
    (net (code "2") (name "+8V") (class "Default")
      (node (ref "C14") (pin "1") (pinfunction "1_1") (pintype "passive"))
      (node (ref "C22") (pin "2") (pinfunction "2_2") (pintype "passive"))
      (node (ref "C45") (pin "1") (pinfunction "1_1") (pintype "passive"))
      (node (ref "D10") (pin "A") (pinfunction "A_A") (pintype "passive"))
      (node (ref "D5") (pin "A") (pinfunction "A_A") (pintype "passive"))
      (node (ref "IC10") (pin "8") (pinfunction "V+_8") (pintype "power_in"))
      (node (ref "IC5") (pin "1") (pinfunction "IN_1") (pintype "input"))
      (node (ref "IC5") (pin "3") (pinfunction "ON/~{OFF}_3") (pintype "input"))
      (node (ref "R4") (pin "1") (pinfunction "1_1") (pintype "passive"))
    )
    (net (code "3") (name "+VAUX") (class "Default")
      (node (ref "X2") (pin "2") (pinfunction "1_2") (pintype "passive"))
    )
    (net (code "4") (name "+VREF") (class "Default")
      (node (ref "C39") (pin "2") (pinfunction "2_2") (pintype "passive"))
      (node (ref "IC8") (pin "25") (pinfunction "VREFSD+_25") (pintype "passive"))
      (node (ref "IC8") (pin "9") (pinfunction "VDDA/VREF+_9") (pintype "passive"))
      (node (ref "IC9") (pin "1") (pinfunction "C_1") (pintype "passive"))
      (node (ref "IC9") (pin "2") (pinfunction "R_2") (pintype "passive"))
      (node (ref "R23") (pin "2") (pinfunction "2_2") (pintype "passive"))
    )
    (net (code "5") (name "-8V") (class "Default")
      (node (ref "C5") (pin "1") (pinfunction "1_1") (pintype "passive"))
      (node (ref "C51") (pin "2") (pinfunction "2_2") (pintype "passive"))
      (node (ref "IC10") (pin "4") (pinfunction "V-_4") (pintype "power_in"))
      (node (ref "R2") (pin "1") (pinfunction "1_1") (pintype "passive"))
    )
    (net (code "6") (name "AGND") (class "Default")
      (node (ref "C39") (pin "1") (pinfunction "1_1") (pintype "passive"))
      (node (ref "IC8") (pin "23") (pinfunction "VSSSD/VREFSD-_23") (pintype "passive"))
      (node (ref "IC8") (pin "8") (pinfunction "VSSA/VREF-_8") (pintype "passive"))
      (node (ref "IC9") (pin "3") (pinfunction "A_3") (pintype "passive"))
      (node (ref "SH2") (pin "1") (pinfunction "GND_A_1") (pintype "bidirectional"))
    )
    (net (code "7") (name "BOOT0") (class "Default")
      (node (ref "IC3") (pin "13") (pinfunction "B2_13") (pintype "output"))
      (node (ref "IC8") (pin "44") (pinfunction "BOOT0_44") (pintype "input"))
      (node (ref "JP1") (pin "2") (pinfunction "2_2") (pintype "passive"))
      (node (ref "R15") (pin "2") (pinfunction "2_2") (pintype "passive"))
    )
    (net (code "8") (name "CC#1") (class "Default")
      (node (ref "IC12") (pin "7") (pinfunction "OUT_7") (pintype "output"))
      (node (ref "IC8") (pin "3") (pinfunction "PC14-OSC32_IN_3") (pintype "bidirectional"))
    )
    (net (code "9") (name "CC#2") (class "Default")
      (node (ref "IC12") (pin "1") (pinfunction "OUT_1") (pintype "output"))
      (node (ref "IC8") (pin "4") (pinfunction "PC15-OSC32_OUT_4") (pintype "bidirectional"))
    )
    (net (code "10") (name "CC_LED#1") (class "Default")
      (node (ref "IC8") (pin "2") (pinfunction "PC13_2") (pintype "bidirectional"))
      (node (ref "Q5") (pin "1") (pinfunction "G_1") (pintype "passive"))
      (node (ref "R49") (pin "2") (pinfunction "2_2") (pintype "passive"))
    )
    (net (code "11") (name "CC_LED#2") (class "Default")
      (node (ref "IC8") (pin "11") (pinfunction "PA1_11") (pintype "bidirectional"))
      (node (ref "Q10") (pin "1") (pinfunction "G_1") (pintype "passive"))
      (node (ref "R73") (pin "2") (pinfunction "2_2") (pintype "passive"))
    )
    (net (code "12") (name "DC_OUT+") (class "Default")
      (node (ref "C3") (pin "2") (pinfunction "2_2") (pintype "passive"))
      (node (ref "C46") (pin "+") (pinfunction "+_+") (pintype "passive"))
      (node (ref "C50") (pin "1") (pinfunction "1_1") (pintype "passive"))
      (node (ref "C52") (pin "1") (pinfunction "1_1") (pintype "passive"))
      (node (ref "C6") (pin "1") (pinfunction "1_1") (pintype "passive"))
      (node (ref "C68") (pin "+") (pinfunction "+_+") (pintype "passive"))
      (node (ref "C71") (pin "1") (pinfunction "1_1") (pintype "passive"))
      (node (ref "C72") (pin "1") (pinfunction "1_1") (pintype "passive"))
      (node (ref "C9") (pin "1") (pinfunction "1_1") (pintype "passive"))
      (node (ref "IC11") (pin "6") (pinfunction "IVINN_6") (pintype "input"))
      (node (ref "IC11") (pin "7") (pinfunction "IVINP_7") (pintype "input"))
      (node (ref "IC13") (pin "6") (pinfunction "IVINN_6") (pintype "input"))
      (node (ref "IC13") (pin "7") (pinfunction "IVINP_7") (pintype "input"))
      (node (ref "IC2") (pin "2") (pinfunction "VIN_2") (pintype "power_in"))
      (node (ref "L1") (pin "4") (pinfunction "2_4") (pintype "passive"))
      (node (ref "Q2") (pin "2") (pinfunction "D_2") (pintype "passive"))
      (node (ref "Q7") (pin "2") (pinfunction "D_2") (pintype "passive"))
      (node (ref "R28") (pin "1") (pinfunction "1_1") (pintype "passive"))
      (node (ref "R29") (pin "1") (pinfunction "1_1") (pintype "passive"))
      (node (ref "R3") (pin "2") (pinfunction "2_2") (pintype "passive"))
      (node (ref "R52") (pin "1") (pinfunction "1_1") (pintype "passive"))
      (node (ref "R53") (pin "1") (pinfunction "1_1") (pintype "passive"))
      (node (ref "ZD1") (pin "C") (pinfunction "C_C") (pintype "passive"))
    )
    (net (code "13") (name "DIB_A0") (class "Default")
      (node (ref "IC4") (pin "1") (pinfunction "A0_1") (pintype "input"))
      (node (ref "R13") (pin "2") (pinfunction "2_2") (pintype "passive"))
      (node (ref "X2") (pin "17") (pinfunction "1_17") (pintype "passive"))
    )
    (net (code "14") (name "DIB_A1") (class "Default")
      (node (ref "IC4") (pin "2") (pinfunction "A1_2") (pintype "input"))
      (node (ref "R12") (pin "2") (pinfunction "2_2") (pintype "passive"))
      (node (ref "X2") (pin "19") (pinfunction "1_19") (pintype "passive"))
    )
    (net (code "15") (name "DIB_A2") (class "Default")
      (node (ref "IC4") (pin "3") (pinfunction "A2_3") (pintype "input"))
      (node (ref "R11") (pin "2") (pinfunction "2_2") (pintype "passive"))
      (node (ref "X2") (pin "18") (pinfunction "1_18") (pintype "passive"))
    )
    (net (code "16") (name "DIB_BOOT0") (class "Default")
      (node (ref "IC3") (pin "4") (pinfunction "A2_4") (pintype "input"))
      (node (ref "IC3") (pin "7") (pinfunction "EN1_7") (pintype "input"))
      (node (ref "X2") (pin "26") (pinfunction "1_26") (pintype "passive"))
    )
    (net (code "17") (name "DIB_CSA") (class "Default")
      (node (ref "IC1") (pin "5") (pinfunction "A4_5") (pintype "input"))
      (node (ref "X2") (pin "9") (pinfunction "1_9") (pintype "passive"))
    )
    (net (code "18") (name "DIB_CSB") (class "Default")
      (node (ref "X2") (pin "12") (pinfunction "1_12") (pintype "passive"))
    )
    (net (code "19") (name "DIB_IRQ") (class "Default")
      (node (ref "IC1") (pin "7") (pinfunction "A6_7") (pintype "output"))
      (node (ref "X2") (pin "10") (pinfunction "1_10") (pintype "passive"))
    )
    (net (code "20") (name "DIB_MISO") (class "Default")
      (node (ref "IC1") (pin "6") (pinfunction "A5_6") (pintype "output"))
      (node (ref "X2") (pin "14") (pinfunction "1_14") (pintype "passive"))
    )
    (net (code "21") (name "DIB_MOSI") (class "Default")
      (node (ref "IC3") (pin "3") (pinfunction "A1_3") (pintype "input"))
      (node (ref "X2") (pin "15") (pinfunction "1_15") (pintype "passive"))
    )
    (net (code "22") (name "DIB_NFAULT") (class "Default")
      (node (ref "X2") (pin "3") (pinfunction "1_3") (pintype "passive"))
    )
    (net (code "23") (name "DIB_NRESET") (class "Default")
      (node (ref "IC1") (pin "2") (pinfunction "A1_2") (pintype "input"))
      (node (ref "X2") (pin "4") (pinfunction "1_4") (pintype "passive"))
    )
    (net (code "24") (name "DIB_SCL") (class "Default")
      (node (ref "IC4") (pin "6") (pinfunction "SCL_6") (pintype "bidirectional"))
      (node (ref "X2") (pin "5") (pinfunction "1_5") (pintype "passive"))
    )
    (net (code "25") (name "DIB_SCLK") (class "Default")
      (node (ref "IC1") (pin "4") (pinfunction "A3_4") (pintype "input"))
      (node (ref "X2") (pin "13") (pinfunction "1_13") (pintype "passive"))
    )
    (net (code "26") (name "DIB_SDA") (class "Default")
      (node (ref "IC4") (pin "5") (pinfunction "SDA_5") (pintype "bidirectional"))
      (node (ref "X2") (pin "8") (pinfunction "1_8") (pintype "passive"))
    )
    (net (code "27") (name "DIB_SYNC") (class "Default")
      (node (ref "IC1") (pin "3") (pinfunction "A2_3") (pintype "input"))
      (node (ref "X2") (pin "6") (pinfunction "1_6") (pintype "passive"))
    )
    (net (code "28") (name "DIB_UART_RX") (class "Default")
      (node (ref "IC3") (pin "6") (pinfunction "A4_6") (pintype "output"))
      (node (ref "X2") (pin "27") (pinfunction "1_27") (pintype "passive"))
    )
    (net (code "29") (name "DIB_UART_TX") (class "Default")
      (node (ref "IC3") (pin "5") (pinfunction "A3_5") (pintype "input"))
      (node (ref "X2") (pin "28") (pinfunction "1_28") (pintype "passive"))
    )
    (net (code "30") (name "FB1") (class "Default")
      (node (ref "IC11") (pin "11") (pinfunction "FB_11") (pintype "input"))
      (node (ref "IC12") (pin "10") (pinfunction "+IN_10") (pintype "input"))
      (node (ref "R39") (pin "1") (pinfunction "1_1") (pintype "passive"))
      (node (ref "R46") (pin "2") (pinfunction "2_2") (pintype "passive"))
      (node (ref "R48") (pin "2") (pinfunction "2_2") (pintype "passive"))
    )
    (net (code "31") (name "FB2") (class "Default")
      (node (ref "IC12") (pin "12") (pinfunction "+IN_12") (pintype "input"))
      (node (ref "IC13") (pin "11") (pinfunction "FB_11") (pintype "input"))
      (node (ref "R63") (pin "1") (pinfunction "1_1") (pintype "passive"))
      (node (ref "R70") (pin "2") (pinfunction "2_2") (pintype "passive"))
      (node (ref "R72") (pin "2") (pinfunction "2_2") (pintype "passive"))
    )
    (net (code "32") (name "GND") (class "Default")
      (node (ref "C12") (pin "2") (pinfunction "2_2") (pintype "passive"))
      (node (ref "C13") (pin "2") (pinfunction "2_2") (pintype "passive"))
      (node (ref "C14") (pin "2") (pinfunction "2_2") (pintype "passive"))
      (node (ref "C15") (pin "2") (pinfunction "2_2") (pintype "passive"))
      (node (ref "C16") (pin "1") (pinfunction "1_1") (pintype "passive"))
      (node (ref "C18") (pin "1") (pinfunction "1_1") (pintype "passive"))
      (node (ref "C19") (pin "1") (pinfunction "1_1") (pintype "passive"))
      (node (ref "C2") (pin "1") (pinfunction "1_1") (pintype "passive"))
      (node (ref "C21") (pin "2") (pinfunction "2_2") (pintype "passive"))
      (node (ref "C22") (pin "1") (pinfunction "1_1") (pintype "passive"))
      (node (ref "C23") (pin "1") (pinfunction "1_1") (pintype "passive"))
      (node (ref "C25") (pin "2") (pinfunction "2_2") (pintype "passive"))
      (node (ref "C26") (pin "2") (pinfunction "2_2") (pintype "passive"))
      (node (ref "C27") (pin "2") (pinfunction "2_2") (pintype "passive"))
      (node (ref "C28") (pin "1") (pinfunction "1_1") (pintype "passive"))
      (node (ref "C29") (pin "2") (pinfunction "2_2") (pintype "passive"))
      (node (ref "C31") (pin "2") (pinfunction "2_2") (pintype "passive"))
      (node (ref "C32") (pin "1") (pinfunction "1_1") (pintype "passive"))
      (node (ref "C33") (pin "1") (pinfunction "1_1") (pintype "passive"))
      (node (ref "C34") (pin "1") (pinfunction "1_1") (pintype "passive"))
      (node (ref "C35") (pin "1") (pinfunction "1_1") (pintype "passive"))
      (node (ref "C37") (pin "1") (pinfunction "1_1") (pintype "passive"))
      (node (ref "C38") (pin "1") (pinfunction "1_1") (pintype "passive"))
      (node (ref "C4") (pin "2") (pinfunction "2_2") (pintype "passive"))
      (node (ref "C40") (pin "1") (pinfunction "1_1") (pintype "passive"))
      (node (ref "C41") (pin "1") (pinfunction "1_1") (pintype "passive"))
      (node (ref "C42") (pin "1") (pinfunction "1_1") (pintype "passive"))
      (node (ref "C43") (pin "1") (pinfunction "1_1") (pintype "passive"))
      (node (ref "C44") (pin "1") (pinfunction "1_1") (pintype "passive"))
      (node (ref "C45") (pin "2") (pinfunction "2_2") (pintype "passive"))
      (node (ref "C46") (pin "-") (pinfunction "-_-") (pintype "passive"))
      (node (ref "C47") (pin "2") (pinfunction "2_2") (pintype "passive"))
      (node (ref "C49") (pin "2") (pinfunction "2_2") (pintype "passive"))
      (node (ref "C5") (pin "2") (pinfunction "2_2") (pintype "passive"))
      (node (ref "C50") (pin "2") (pinfunction "2_2") (pintype "passive"))
      (node (ref "C51") (pin "1") (pinfunction "1_1") (pintype "passive"))
      (node (ref "C52") (pin "2") (pinfunction "2_2") (pintype "passive"))
      (node (ref "C53") (pin "2") (pinfunction "2_2") (pintype "passive"))
      (node (ref "C55") (pin "2") (pinfunction "2_2") (pintype "passive"))
      (node (ref "C57") (pin "2") (pinfunction "2_2") (pintype "passive"))
      (node (ref "C59") (pin "2") (pinfunction "2_2") (pintype "passive"))
      (node (ref "C6") (pin "2") (pinfunction "2_2") (pintype "passive"))
      (node (ref "C60") (pin "2") (pinfunction "2_2") (pintype "passive"))
      (node (ref "C61") (pin "2") (pinfunction "-_2") (pintype "passive"))
      (node (ref "C62") (pin "-") (pinfunction "-_-") (pintype "passive"))
      (node (ref "C63") (pin "2") (pinfunction "2_2") (pintype "passive"))
      (node (ref "C64") (pin "1") (pinfunction "1_1") (pintype "passive"))
      (node (ref "C66") (pin "1") (pinfunction "1_1") (pintype "passive"))
      (node (ref "C68") (pin "-") (pinfunction "-_-") (pintype "passive"))
      (node (ref "C70") (pin "2") (pinfunction "2_2") (pintype "passive"))
      (node (ref "C71") (pin "2") (pinfunction "2_2") (pintype "passive"))
      (node (ref "C72") (pin "2") (pinfunction "2_2") (pintype "passive"))
      (node (ref "C73") (pin "2") (pinfunction "2_2") (pintype "passive"))
      (node (ref "C75") (pin "2") (pinfunction "2_2") (pintype "passive"))
      (node (ref "C77") (pin "2") (pinfunction "2_2") (pintype "passive"))
      (node (ref "C79") (pin "2") (pinfunction "2_2") (pintype "passive"))
      (node (ref "C8") (pin "1") (pinfunction "1_1") (pintype "passive"))
      (node (ref "C80") (pin "2") (pinfunction "2_2") (pintype "passive"))
      (node (ref "C81") (pin "2") (pinfunction "-_2") (pintype "passive"))
      (node (ref "C82") (pin "-") (pinfunction "-_-") (pintype "passive"))
      (node (ref "C83") (pin "2") (pinfunction "2_2") (pintype "passive"))
      (node (ref "C84") (pin "1") (pinfunction "1_1") (pintype "passive"))
      (node (ref "C86") (pin "1") (pinfunction "1_1") (pintype "passive"))
      (node (ref "C9") (pin "2") (pinfunction "2_2") (pintype "passive"))
      (node (ref "CH1") (pin "GND") (pinfunction "GND_GND") (pintype "bidirectional"))
      (node (ref "CH2") (pin "GND") (pinfunction "GND_GND") (pintype "bidirectional"))
      (node (ref "D12") (pin "A") (pinfunction "A_A") (pintype "passive"))
      (node (ref "D2") (pin "A") (pinfunction "A_A") (pintype "passive"))
      (node (ref "D7") (pin "A") (pinfunction "A_A") (pintype "passive"))
      (node (ref "GND") (pin "1") (pinfunction "P$1_1") (pintype "bidirectional"))
      (node (ref "IC1") (pin "9") (pinfunction "GND2_9") (pintype "passive"))
      (node (ref "IC11") (pin "12") (pinfunction "GND_12") (pintype "passive"))
      (node (ref "IC11") (pin "21") (pinfunction "SYNC_21") (pintype "input"))
      (node (ref "IC11") (pin "23") (pinfunction "GND_23") (pintype "passive"))
      (node (ref "IC11") (pin "28") (pinfunction "GND_28") (pintype "passive"))
      (node (ref "IC11") (pin "TP") (pinfunction "GND_PAD_TP") (pintype "passive"))
      (node (ref "IC12") (pin "11") (pinfunction "V-_11") (pintype "power_in"))
      (node (ref "IC13") (pin "12") (pinfunction "GND_12") (pintype "passive"))
      (node (ref "IC13") (pin "21") (pinfunction "SYNC_21") (pintype "input"))
      (node (ref "IC13") (pin "23") (pinfunction "GND_23") (pintype "passive"))
      (node (ref "IC13") (pin "28") (pinfunction "GND_28") (pintype "passive"))
      (node (ref "IC13") (pin "TP") (pinfunction "GND_PAD_TP") (pintype "passive"))
      (node (ref "IC2") (pin "9") (pinfunction "GND_9") (pintype "passive"))
      (node (ref "IC2") (pin "TP") (pinfunction "TP_TP") (pintype "passive"))
      (node (ref "IC3") (pin "15") (pinfunction "GND2_15") (pintype "passive"))
      (node (ref "IC3") (pin "9") (pinfunction "GND2_2_9") (pintype "passive"))
      (node (ref "IC5") (pin "2") (pinfunction "GND_2") (pintype "passive"))
      (node (ref "IC6") (pin "2") (pinfunction "V-_2") (pintype "power_in"))
      (node (ref "IC7") (pin "3") (pinfunction "GND_3") (pintype "power_in"))
      (node (ref "IC8") (pin "47") (pinfunction "VSS_1_47") (pintype "bidirectional"))
      (node (ref "J3") (pin "1") (pinfunction "1_1") (pintype "passive"))
      (node (ref "J3") (pin "1.1") (pinfunction "1_1.1") (pintype "passive"))
      (node (ref "J5") (pin "1") (pinfunction "1_1") (pintype "passive"))
      (node (ref "J5") (pin "1.1") (pinfunction "1_1.1") (pintype "passive"))
      (node (ref "L1") (pin "2") (pinfunction "2_2") (pintype "passive"))
      (node (ref "LED1") (pin "CC") (pinfunction "C_CC") (pintype "passive"))
      (node (ref "LED2") (pin "CC") (pinfunction "C_CC") (pintype "passive"))
      (node (ref "Q3") (pin "3") (pinfunction "S_3") (pintype "passive"))
      (node (ref "Q8") (pin "3") (pinfunction "S_3") (pintype "passive"))
      (node (ref "R10") (pin "1") (pinfunction "1_1") (pintype "passive"))
      (node (ref "R15") (pin "1") (pinfunction "1_1") (pintype "passive"))
      (node (ref "R19") (pin "1") (pinfunction "1_1") (pintype "passive"))
      (node (ref "R21") (pin "2") (pinfunction "2_2") (pintype "passive"))
      (node (ref "R22") (pin "2") (pinfunction "2_2") (pintype "passive"))
      (node (ref "R30") (pin "1") (pinfunction "1_1") (pintype "passive"))
      (node (ref "R33") (pin "1") (pinfunction "1_1") (pintype "passive"))
      (node (ref "R37") (pin "1") (pinfunction "1_1") (pintype "passive"))
      (node (ref "R41") (pin "2") (pinfunction "2_2") (pintype "passive"))
      (node (ref "R42") (pin "1") (pinfunction "1_1") (pintype "passive"))
      (node (ref "R45") (pin "1") (pinfunction "1_1") (pintype "passive"))
      (node (ref "R46") (pin "1") (pinfunction "1_1") (pintype "passive"))
      (node (ref "R47") (pin "1") (pinfunction "1_1") (pintype "passive"))
      (node (ref "R5") (pin "1") (pinfunction "1_1") (pintype "passive"))
      (node (ref "R51") (pin "1") (pinfunction "1_1") (pintype "passive"))
      (node (ref "R54") (pin "1") (pinfunction "1_1") (pintype "passive"))
      (node (ref "R57") (pin "1") (pinfunction "1_1") (pintype "passive"))
      (node (ref "R6") (pin "1") (pinfunction "1_1") (pintype "passive"))
      (node (ref "R61") (pin "1") (pinfunction "1_1") (pintype "passive"))
      (node (ref "R65") (pin "2") (pinfunction "2_2") (pintype "passive"))
      (node (ref "R66") (pin "1") (pinfunction "1_1") (pintype "passive"))
      (node (ref "R69") (pin "1") (pinfunction "1_1") (pintype "passive"))
      (node (ref "R70") (pin "1") (pinfunction "1_1") (pintype "passive"))
      (node (ref "R71") (pin "1") (pinfunction "1_1") (pintype "passive"))
      (node (ref "R75") (pin "1") (pinfunction "1_1") (pintype "passive"))
      (node (ref "R76") (pin "2") (pinfunction "2_2") (pintype "passive"))
      (node (ref "R77") (pin "2") (pinfunction "2_2") (pintype "passive"))
      (node (ref "R8") (pin "1") (pinfunction "1_1") (pintype "passive"))
      (node (ref "SH2") (pin "2") (pinfunction "GND_B_2") (pintype "bidirectional"))
      (node (ref "TR1") (pin "4") (pinfunction "4_4") (pintype "passive"))
      (node (ref "X3") (pin "3") (pinfunction "S_3") (pintype "passive"))
      (node (ref "X4") (pin "1") (pinfunction "1_1") (pintype "passive"))
      (node (ref "X4") (pin "10") (pinfunction "1_10") (pintype "passive"))
      (node (ref "X4") (pin "2") (pinfunction "1_2") (pintype "passive"))
      (node (ref "X4") (pin "3") (pinfunction "1_3") (pintype "passive"))
      (node (ref "X4") (pin "4") (pinfunction "1_4") (pintype "passive"))
      (node (ref "X4") (pin "5") (pinfunction "1_5") (pintype "passive"))
      (node (ref "X4") (pin "6") (pinfunction "1_6") (pintype "passive"))
      (node (ref "X4") (pin "7") (pinfunction "1_7") (pintype "passive"))
      (node (ref "X4") (pin "8") (pinfunction "1_8") (pintype "passive"))
      (node (ref "X4") (pin "9") (pinfunction "1_9") (pintype "passive"))
      (node (ref "ZD1") (pin "A") (pinfunction "A_A") (pintype "passive"))
      (node (ref "ZD3") (pin "A") (pinfunction "A_A") (pintype "passive"))
      (node (ref "ZD5") (pin "A") (pinfunction "A_A") (pintype "passive"))
    )
    (net (code "33") (name "GNDIO") (class "Default")
      (node (ref "C17") (pin "2") (pinfunction "2_2") (pintype "passive"))
      (node (ref "C20") (pin "1") (pinfunction "1_1") (pintype "passive"))
      (node (ref "C7") (pin "2") (pinfunction "2_2") (pintype "passive"))
      (node (ref "IC1") (pin "8") (pinfunction "GND1_8") (pintype "passive"))
      (node (ref "IC3") (pin "2") (pinfunction "GND1_2_2") (pintype "passive"))
      (node (ref "IC3") (pin "8") (pinfunction "GND1_8") (pintype "passive"))
      (node (ref "IC4") (pin "4") (pinfunction "GND_4") (pintype "passive"))
      (node (ref "IC4") (pin "7") (pinfunction "WP_7") (pintype "input"))
      (node (ref "X2") (pin "11") (pinfunction "1_11") (pintype "passive"))
      (node (ref "X2") (pin "16") (pinfunction "1_16") (pintype "passive"))
      (node (ref "X2") (pin "20") (pinfunction "1_20") (pintype "passive"))
      (node (ref "X2") (pin "25") (pinfunction "1_25") (pintype "passive"))
      (node (ref "X2") (pin "7") (pinfunction "1_7") (pintype "passive"))
    )
    (net (code "34") (name "INTVCC1") (class "Default")
      (node (ref "C55") (pin "1") (pinfunction "1_1") (pintype "passive"))
      (node (ref "D6") (pin "A") (pinfunction "A_A") (pintype "passive"))
      (node (ref "IC11") (pin "2") (pinfunction "INTVCC_2") (pintype "passive"))
      (node (ref "R43") (pin "1") (pinfunction "1_1") (pintype "passive"))
      (node (ref "R44") (pin "2") (pinfunction "2_2") (pintype "passive"))
    )
    (net (code "35") (name "INTVCC2") (class "Default")
      (node (ref "C75") (pin "1") (pinfunction "1_1") (pintype "passive"))
      (node (ref "D11") (pin "A") (pinfunction "A_A") (pintype "passive"))
      (node (ref "IC13") (pin "2") (pinfunction "INTVCC_2") (pintype "passive"))
      (node (ref "R67") (pin "1") (pinfunction "1_1") (pintype "passive"))
      (node (ref "R68") (pin "2") (pinfunction "2_2") (pintype "passive"))
    )
    (net (code "36") (name "IRQ") (class "Default")
      (node (ref "IC1") (pin "10") (pinfunction "B6_10") (pintype "input"))
      (node (ref "IC8") (pin "33") (pinfunction "PA12_33") (pintype "bidirectional"))
    )
    (net (code "37") (name "I_MON#1") (class "Default")
      (node (ref "C42") (pin "2") (pinfunction "2_2") (pintype "passive"))
      (node (ref "IC8") (pin "19") (pinfunction "PB1_19") (pintype "bidirectional"))
      (node (ref "R25") (pin "1") (pinfunction "1_1") (pintype "passive"))
    )
    (net (code "38") (name "I_MON#2") (class "Default")
      (node (ref "C44") (pin "2") (pinfunction "2_2") (pintype "passive"))
      (node (ref "IC8") (pin "21") (pinfunction "PE8_21") (pintype "bidirectional"))
      (node (ref "R27") (pin "1") (pinfunction "1_1") (pintype "passive"))
    )
    (net (code "39") (name "I_MON1") (class "Default")
      (node (ref "C64") (pin "2") (pinfunction "2_2") (pintype "passive"))
      (node (ref "R25") (pin "2") (pinfunction "2_2") (pintype "passive"))
      (node (ref "R38") (pin "1") (pinfunction "1_1") (pintype "passive"))
    )
    (net (code "40") (name "I_MON2") (class "Default")
      (node (ref "C84") (pin "2") (pinfunction "2_2") (pintype "passive"))
      (node (ref "R27") (pin "2") (pinfunction "2_2") (pintype "passive"))
      (node (ref "R62") (pin "1") (pinfunction "1_1") (pintype "passive"))
    )
    (net (code "41") (name "I_SET#1") (class "Default")
      (node (ref "I_SET1") (pin "1") (pinfunction "1_1") (pintype "passive"))
      (node (ref "R32") (pin "1") (pinfunction "1_1") (pintype "passive"))
    )
    (net (code "42") (name "I_SET#2") (class "Default")
      (node (ref "I_SET2") (pin "1") (pinfunction "1_1") (pintype "passive"))
      (node (ref "R56") (pin "1") (pinfunction "1_1") (pintype "passive"))
    )
    (net (code "43") (name "I_SET_OUT#1") (class "Default")
      (node (ref "IC6") (pin "1") (pinfunction "I_1") (pintype "input"))
      (node (ref "IC8") (pin "45") (pinfunction "PB8_45") (pintype "bidirectional"))
      (node (ref "R14") (pin "2") (pinfunction "2_2") (pintype "passive"))
    )
    (net (code "44") (name "I_SET_OUT#2") (class "Default")
      (node (ref "IC6") (pin "3") (pinfunction "I_3") (pintype "input"))
      (node (ref "IC8") (pin "46") (pinfunction "PB9_46") (pintype "bidirectional"))
      (node (ref "R17") (pin "2") (pinfunction "2_2") (pintype "passive"))
    )
    (net (code "45") (name "MISO") (class "Default")
      (node (ref "IC1") (pin "11") (pinfunction "B5_11") (pintype "input"))
      (node (ref "IC8") (pin "26") (pinfunction "PB14_26") (pintype "bidirectional"))
    )
    (net (code "46") (name "MOSI") (class "Default")
      (node (ref "IC8") (pin "27") (pinfunction "PB15_27") (pintype "bidirectional"))
      (node (ref "RN1") (pin "5") (pinfunction "2_5") (pintype "passive"))
    )
    (net (code "47") (name "NRST") (class "Default")
      (node (ref "C36") (pin "1") (pinfunction "1_1") (pintype "passive"))
      (node (ref "IC8") (pin "7") (pinfunction "NRST_7") (pintype "input"))
      (node (ref "JP3") (pin "2") (pinfunction "2_2") (pintype "passive"))
      (node (ref "R20") (pin "2") (pinfunction "2_2") (pintype "passive"))
      (node (ref "RN2") (pin "3") (pinfunction "1_3") (pintype "passive"))
    )
    (net (code "48") (name "NSS") (class "Default")
      (node (ref "IC8") (pin "32") (pinfunction "PA11_32") (pintype "bidirectional"))
      (node (ref "RN1") (pin "6") (pinfunction "2_6") (pintype "passive"))
    )
    (net (code "49") (name "Net-(C4-Pad1)") (class "Default")
      (node (ref "C4") (pin "1") (pinfunction "1_1") (pintype "passive"))
      (node (ref "D1") (pin "A") (pinfunction "A_A") (pintype "passive"))
      (node (ref "R2") (pin "2") (pinfunction "2_2") (pintype "passive"))
    )
    (net (code "50") (name "Net-(C11-Pad2)") (class "Default")
      (node (ref "C11") (pin "2") (pinfunction "2_2") (pintype "passive"))
      (node (ref "R5") (pin "2") (pinfunction "2_2") (pintype "passive"))
    )
    (net (code "51") (name "Net-(C12-Pad1)") (class "Default")
      (node (ref "C12") (pin "1") (pinfunction "1_1") (pintype "passive"))
      (node (ref "C13") (pin "1") (pinfunction "1_1") (pintype "passive"))
      (node (ref "R4") (pin "2") (pinfunction "2_2") (pintype "passive"))
      (node (ref "R7") (pin "2") (pinfunction "2_2") (pintype "passive"))
      (node (ref "TR1") (pin "3") (pinfunction "3_3") (pintype "passive"))
    )
    (net (code "52") (name "Net-(C19-Pad2)") (class "Default")
      (node (ref "C19") (pin "2") (pinfunction "2_2") (pintype "passive"))
      (node (ref "R9") (pin "1") (pinfunction "1_1") (pintype "passive"))
    )
    (net (code "53") (name "Net-(C24-Pad1)") (class "Default")
      (node (ref "C24") (pin "1") (pinfunction "1_1") (pintype "passive"))
      (node (ref "C26") (pin "1") (pinfunction "1_1") (pintype "passive"))
      (node (ref "I_SET1") (pin "2") (pinfunction "2_2") (pintype "passive"))
      (node (ref "R14") (pin "1") (pinfunction "1_1") (pintype "passive"))
    )
    (net (code "54") (name "Net-(C24-Pad2)") (class "Default")
      (node (ref "C24") (pin "2") (pinfunction "2_2") (pintype "passive"))
      (node (ref "R16") (pin "1") (pinfunction "1_1") (pintype "passive"))
    )
    (net (code "55") (name "Net-(C30-Pad1)") (class "Default")
      (node (ref "C30") (pin "1") (pinfunction "1_1") (pintype "passive"))
      (node (ref "C31") (pin "1") (pinfunction "1_1") (pintype "passive"))
      (node (ref "I_SET2") (pin "2") (pinfunction "2_2") (pintype "passive"))
      (node (ref "R17") (pin "1") (pinfunction "1_1") (pintype "passive"))
    )
    (net (code "56") (name "Net-(C30-Pad2)") (class "Default")
      (node (ref "C30") (pin "2") (pinfunction "2_2") (pintype "passive"))
      (node (ref "R18") (pin "1") (pinfunction "1_1") (pintype "passive"))
    )
    (net (code "57") (name "Net-(C58-Pad2)") (class "Default")
      (node (ref "C58") (pin "2") (pinfunction "2_2") (pintype "passive"))
      (node (ref "R37") (pin "2") (pinfunction "2_2") (pintype "passive"))
    )
    (net (code "58") (name "Net-(C67-Pad1)") (class "Default")
      (node (ref "C67") (pin "1") (pinfunction "1_1") (pintype "passive"))
      (node (ref "R45") (pin "2") (pinfunction "2_2") (pintype "passive"))
    )
    (net (code "59") (name "Net-(C78-Pad2)") (class "Default")
      (node (ref "C78") (pin "2") (pinfunction "2_2") (pintype "passive"))
      (node (ref "R61") (pin "2") (pinfunction "2_2") (pintype "passive"))
    )
    (net (code "60") (name "Net-(C87-Pad1)") (class "Default")
      (node (ref "C87") (pin "1") (pinfunction "1_1") (pintype "passive"))
      (node (ref "R69") (pin "2") (pinfunction "2_2") (pintype "passive"))
    )
    (net (code "61") (name "Net-(D1-PadC)") (class "Default")
      (node (ref "D1") (pin "C") (pinfunction "C_C") (pintype "passive"))
      (node (ref "TR1") (pin "2") (pinfunction "2_2") (pintype "passive"))
    )
    (net (code "62") (name "Net-(IC1-B2)") (class "Default")
      (node (ref "IC1") (pin "14") (pinfunction "B2_14") (pintype "output"))
      (node (ref "RN1") (pin "1") (pinfunction "1_1") (pintype "passive"))
    )
    (net (code "63") (name "Net-(IC1-B3)") (class "Default")
      (node (ref "IC1") (pin "13") (pinfunction "B3_13") (pintype "output"))
      (node (ref "RN1") (pin "2") (pinfunction "1_2") (pintype "passive"))
    )
    (net (code "64") (name "Net-(IC1-B4)") (class "Default")
      (node (ref "IC1") (pin "12") (pinfunction "B4_12") (pintype "output"))
      (node (ref "RN1") (pin "3") (pinfunction "1_3") (pintype "passive"))
    )
    (net (code "65") (name "Net-(IC2-BOOT)") (class "Default")
      (node (ref "C10") (pin "2") (pinfunction "2_2") (pintype "passive"))
      (node (ref "IC2") (pin "1") (pinfunction "BOOT_1") (pintype "output"))
    )
    (net (code "66") (name "Net-(IC2-COMP)") (class "Default")
      (node (ref "C16") (pin "2") (pinfunction "2_2") (pintype "passive"))
      (node (ref "IC2") (pin "8") (pinfunction "COMP_8") (pintype "output"))
      (node (ref "R9") (pin "2") (pinfunction "2_2") (pintype "passive"))
    )
    (net (code "67") (name "Net-(IC2-EN)") (class "Default")
      (node (ref "IC2") (pin "3") (pinfunction "EN_3") (pintype "input"))
      (node (ref "R3") (pin "1") (pinfunction "1_1") (pintype "passive"))
      (node (ref "R6") (pin "2") (pinfunction "2_2") (pintype "passive"))
    )
    (net (code "68") (name "Net-(IC2-PH)") (class "Default")
      (node (ref "C10") (pin "1") (pinfunction "1_1") (pintype "passive"))
      (node (ref "C11") (pin "1") (pinfunction "1_1") (pintype "passive"))
      (node (ref "D2") (pin "C") (pinfunction "C_C") (pintype "passive"))
      (node (ref "IC2") (pin "10") (pinfunction "PH_10") (pintype "input"))
      (node (ref "TR1") (pin "1") (pinfunction "1_1") (pintype "passive"))
    )
    (net (code "69") (name "Net-(IC2-RT{slash}CLK)") (class "Default")
      (node (ref "IC2") (pin "5") (pinfunction "RT/CLK_5") (pintype "input"))
      (node (ref "R8") (pin "2") (pinfunction "2_2") (pintype "passive"))
    )
    (net (code "70") (name "Net-(IC2-SS{slash}TR)") (class "Default")
      (node (ref "C15") (pin "1") (pinfunction "1_1") (pintype "passive"))
      (node (ref "IC2") (pin "4") (pinfunction "SS/TR_4") (pintype "input"))
    )
    (net (code "71") (name "Net-(IC2-VSENSE)") (class "Default")
      (node (ref "IC2") (pin "7") (pinfunction "VSENSE_7") (pintype "input"))
      (node (ref "R10") (pin "2") (pinfunction "2_2") (pintype "passive"))
      (node (ref "R7") (pin "1") (pinfunction "1_1") (pintype "passive"))
    )
    (net (code "72") (name "Net-(IC3-B1)") (class "Default")
      (node (ref "IC3") (pin "14") (pinfunction "B1_14") (pintype "output"))
      (node (ref "RN1") (pin "4") (pinfunction "1_4") (pintype "passive"))
    )
    (net (code "73") (name "Net-(IC5-BYPASS)") (class "Default")
      (node (ref "C23") (pin "2") (pinfunction "2_2") (pintype "passive"))
      (node (ref "IC5") (pin "4") (pinfunction "BYPASS_4") (pintype "passive"))
    )
    (net (code "74") (name "Net-(IC6A-O)") (class "Default")
      (node (ref "IC6") (pin "6") (pinfunction "O_6") (pintype "output"))
      (node (ref "R16") (pin "2") (pinfunction "2_2") (pintype "passive"))
    )
    (net (code "75") (name "Net-(IC6B-O)") (class "Default")
      (node (ref "IC6") (pin "4") (pinfunction "O_4") (pintype "output"))
      (node (ref "R18") (pin "2") (pinfunction "2_2") (pintype "passive"))
    )
    (net (code "76") (name "Net-(IC7-IO1)") (class "Default")
      (node (ref "IC7") (pin "1") (pinfunction "IO1_1") (pintype "bidirectional"))
      (node (ref "RN2") (pin "8") (pinfunction "2_8") (pintype "passive"))
      (node (ref "X3") (pin "6") (pinfunction "S_6") (pintype "passive"))
    )
    (net (code "77") (name "Net-(IC7-IO2)") (class "Default")
      (node (ref "IC7") (pin "2") (pinfunction "IO2_2") (pintype "bidirectional"))
      (node (ref "RN2") (pin "6") (pinfunction "2_6") (pintype "passive"))
      (node (ref "X3") (pin "5") (pinfunction "S_5") (pintype "passive"))
    )
    (net (code "78") (name "Net-(IC8-PB5)") (class "Default")
      (node (ref "IC8") (pin "41") (pinfunction "PB5_41") (pintype "bidirectional"))
      (node (ref "OE#1") (pin "1") (pinfunction "1_1") (pintype "passive"))
    )
    (net (code "79") (name "Net-(IC8-PB6)") (class "Default")
      (node (ref "IC8") (pin "42") (pinfunction "PB6_42") (pintype "bidirectional"))
      (node (ref "OE#2") (pin "1") (pinfunction "1_1") (pintype "passive"))
    )
    (net (code "80") (name "Net-(IC8-PF0-OSC_IN)") (class "Default")
      (node (ref "C32") (pin "2") (pinfunction "2_2") (pintype "passive"))
      (node (ref "IC8") (pin "5") (pinfunction "PF0-OSC_IN_5") (pintype "bidirectional"))
      (node (ref "Y1") (pin "3") (pinfunction "2_3") (pintype "passive"))
    )
    (net (code "81") (name "Net-(IC8-PF1-OSC_OUT)") (class "Default")
      (node (ref "C33") (pin "2") (pinfunction "2_2") (pintype "passive"))
      (node (ref "IC8") (pin "6") (pinfunction "PF1-OSC_OUT_6") (pintype "bidirectional"))
      (node (ref "Y1") (pin "1") (pinfunction "1_1") (pintype "passive"))
    )
    (net (code "82") (name "Net-(IC10A-+IN)") (class "Default")
      (node (ref "IC10") (pin "3") (pinfunction "+IN_3") (pintype "input"))
      (node (ref "R56") (pin "2") (pinfunction "2_2") (pintype "passive"))
      (node (ref "R57") (pin "2") (pinfunction "2_2") (pintype "passive"))
    )
    (net (code "83") (name "Net-(IC10A--IN)") (class "Default")
      (node (ref "C69") (pin "2") (pinfunction "2_2") (pintype "passive"))
      (node (ref "IC10") (pin "2") (pinfunction "-IN_2") (pintype "input"))
      (node (ref "R54") (pin "2") (pinfunction "2_2") (pintype "passive"))
      (node (ref "R55") (pin "1") (pinfunction "1_1") (pintype "passive"))
    )
    (net (code "84") (name "Net-(IC10A-OUT)") (class "Default")
      (node (ref "C69") (pin "1") (pinfunction "1_1") (pintype "passive"))
      (node (ref "IC10") (pin "1") (pinfunction "OUT_1") (pintype "output"))
      (node (ref "IC13") (pin "14") (pinfunction "CTRL1_14") (pintype "input"))
      (node (ref "R55") (pin "2") (pinfunction "2_2") (pintype "passive"))
    )
    (net (code "85") (name "Net-(IC10B-+IN)") (class "Default")
      (node (ref "IC10") (pin "5") (pinfunction "+IN_5") (pintype "input"))
      (node (ref "R32") (pin "2") (pinfunction "2_2") (pintype "passive"))
      (node (ref "R33") (pin "2") (pinfunction "2_2") (pintype "passive"))
    )
    (net (code "86") (name "Net-(IC10B--IN)") (class "Default")
      (node (ref "C48") (pin "2") (pinfunction "2_2") (pintype "passive"))
      (node (ref "IC10") (pin "6") (pinfunction "-IN_6") (pintype "input"))
      (node (ref "R30") (pin "2") (pinfunction "2_2") (pintype "passive"))
      (node (ref "R31") (pin "1") (pinfunction "1_1") (pintype "passive"))
    )
    (net (code "87") (name "Net-(IC10B-OUT)") (class "Default")
      (node (ref "C48") (pin "1") (pinfunction "1_1") (pintype "passive"))
      (node (ref "IC10") (pin "7") (pinfunction "OUT_7") (pintype "output"))
      (node (ref "IC11") (pin "14") (pinfunction "CTRL1_14") (pintype "input"))
      (node (ref "R31") (pin "2") (pinfunction "2_2") (pintype "passive"))
    )
    (net (code "88") (name "Net-(IC11-BG)") (class "Default")
      (node (ref "IC11") (pin "1") (pinfunction "BG_1") (pintype "output"))
      (node (ref "Q3") (pin "1") (pinfunction "G_1") (pintype "passive"))
    )
    (net (code "89") (name "Net-(IC11-BOOST)") (class "Default")
      (node (ref "C54") (pin "1") (pinfunction "1_1") (pintype "passive"))
      (node (ref "D6") (pin "C") (pinfunction "C_C") (pintype "passive"))
      (node (ref "IC11") (pin "27") (pinfunction "BOOST_27") (pintype "passive"))
    )
    (net (code "90") (name "Net-(IC11-ISMON)") (class "Default")
      (node (ref "IC11") (pin "19") (pinfunction "ISMON_19") (pintype "output"))
      (node (ref "R38") (pin "2") (pinfunction "2_2") (pintype "passive"))
    )
    (net (code "91") (name "Net-(IC11-PWM)") (class "Default")
      (node (ref "IC11") (pin "22") (pinfunction "PWM_22") (pintype "input"))
      (node (ref "R43") (pin "2") (pinfunction "2_2") (pintype "passive"))
    )
    (net (code "92") (name "Net-(IC11-RT)") (class "Default")
      (node (ref "IC11") (pin "20") (pinfunction "RT_20") (pintype "input"))
      (node (ref "R42") (pin "2") (pinfunction "2_2") (pintype "passive"))
    )
    (net (code "93") (name "Net-(IC11-SENSE+)") (class "Default")
      (node (ref "C65") (pin "1") (pinfunction "1_1") (pintype "passive"))
      (node (ref "IC11") (pin "17") (pinfunction "SENSE+_17") (pintype "input"))
      (node (ref "R35") (pin "1") (pinfunction "1_1") (pintype "passive"))
    )
    (net (code "94") (name "Net-(IC11-SENSE-)") (class "Default")
      (node (ref "C65") (pin "2") (pinfunction "2_2") (pintype "passive"))
      (node (ref "IC11") (pin "16") (pinfunction "SENSE-_16") (pintype "input"))
      (node (ref "R36") (pin "1") (pinfunction "1_1") (pintype "passive"))
    )
    (net (code "95") (name "Net-(IC11-SS)") (class "Default")
      (node (ref "C66") (pin "2") (pinfunction "2_2") (pintype "passive"))
      (node (ref "IC11") (pin "15") (pinfunction "SS_15") (pintype "input"))
    )
    (net (code "96") (name "Net-(IC11-SW)") (class "Default")
      (node (ref "C54") (pin "2") (pinfunction "2_2") (pintype "passive"))
      (node (ref "C58") (pin "1") (pinfunction "1_1") (pintype "passive"))
      (node (ref "D7") (pin "C") (pinfunction "C_C") (pintype "passive"))
      (node (ref "IC11") (pin "26") (pinfunction "SW_26") (pintype "output"))
      (node (ref "L2") (pin "1") (pinfunction "1_1") (pintype "passive"))
      (node (ref "Q2") (pin "3") (pinfunction "S_3") (pintype "passive"))
      (node (ref "Q3") (pin "2") (pinfunction "D_2") (pintype "passive"))
    )
    (net (code "97") (name "Net-(IC11-TG)") (class "Default")
      (node (ref "IC11") (pin "25") (pinfunction "TG_25") (pintype "output"))
      (node (ref "Q2") (pin "1") (pinfunction "G_1") (pintype "passive"))
    )
    (net (code "98") (name "Net-(IC11-VC)") (class "Default")
      (node (ref "C67") (pin "2") (pinfunction "2_2") (pintype "passive"))
      (node (ref "IC11") (pin "18") (pinfunction "VC_18") (pintype "passive"))
    )
    (net (code "99") (name "Net-(IC11-VIN)") (class "Default")
      (node (ref "C49") (pin "1") (pinfunction "1_1") (pintype "passive"))
      (node (ref "D3") (pin "C") (pinfunction "C_C") (pintype "passive"))
      (node (ref "D5") (pin "C") (pinfunction "C_C") (pintype "passive"))
      (node (ref "IC11") (pin "3") (pinfunction "VIN_3") (pintype "passive"))
    )
    (net (code "100") (name "Net-(IC11-~{FAULT})") (class "Default")
      (node (ref "IC11") (pin "9") (pinfunction "~{FAULT}_9") (pintype "output"))
      (node (ref "R44") (pin "1") (pinfunction "1_1") (pintype "passive"))
    )
    (net (code "101") (name "Net-(IC12A-+IN)") (class "Default")
      (node (ref "IC12") (pin "3") (pinfunction "+IN_3") (pintype "input"))
      (node (ref "R74") (pin "1") (pinfunction "1_1") (pintype "passive"))
      (node (ref "R75") (pin "2") (pinfunction "2_2") (pintype "passive"))
    )
    (net (code "102") (name "Net-(IC12A--IN)") (class "Default")
      (node (ref "IC12") (pin "13") (pinfunction "-IN_13") (pintype "input"))
      (node (ref "IC12") (pin "14") (pinfunction "OUT_14") (pintype "output"))
      (node (ref "IC12") (pin "2") (pinfunction "-IN_2") (pintype "input"))
    )
    (net (code "103") (name "Net-(IC12B-+IN)") (class "Default")
      (node (ref "IC12") (pin "5") (pinfunction "+IN_5") (pintype "input"))
      (node (ref "R50") (pin "1") (pinfunction "1_1") (pintype "passive"))
      (node (ref "R51") (pin "2") (pinfunction "2_2") (pintype "passive"))
    )
    (net (code "104") (name "Net-(IC12B--IN)") (class "Default")
      (node (ref "IC12") (pin "6") (pinfunction "-IN_6") (pintype "input"))
      (node (ref "IC12") (pin "8") (pinfunction "OUT_8") (pintype "output"))
      (node (ref "IC12") (pin "9") (pinfunction "-IN_9") (pintype "input"))
    )
    (net (code "105") (name "Net-(IC13-BG)") (class "Default")
      (node (ref "IC13") (pin "1") (pinfunction "BG_1") (pintype "output"))
      (node (ref "Q8") (pin "1") (pinfunction "G_1") (pintype "passive"))
    )
    (net (code "106") (name "Net-(IC13-BOOST)") (class "Default")
      (node (ref "C74") (pin "1") (pinfunction "1_1") (pintype "passive"))
      (node (ref "D11") (pin "C") (pinfunction "C_C") (pintype "passive"))
      (node (ref "IC13") (pin "27") (pinfunction "BOOST_27") (pintype "passive"))
    )
    (net (code "107") (name "Net-(IC13-ISMON)") (class "Default")
      (node (ref "IC13") (pin "19") (pinfunction "ISMON_19") (pintype "output"))
      (node (ref "R62") (pin "2") (pinfunction "2_2") (pintype "passive"))
    )
    (net (code "108") (name "Net-(IC13-PWM)") (class "Default")
      (node (ref "IC13") (pin "22") (pinfunction "PWM_22") (pintype "input"))
      (node (ref "R67") (pin "2") (pinfunction "2_2") (pintype "passive"))
    )
    (net (code "109") (name "Net-(IC13-RT)") (class "Default")
      (node (ref "IC13") (pin "20") (pinfunction "RT_20") (pintype "input"))
      (node (ref "R66") (pin "2") (pinfunction "2_2") (pintype "passive"))
    )
    (net (code "110") (name "Net-(IC13-SENSE+)") (class "Default")
      (node (ref "C85") (pin "1") (pinfunction "1_1") (pintype "passive"))
      (node (ref "IC13") (pin "17") (pinfunction "SENSE+_17") (pintype "input"))
      (node (ref "R59") (pin "1") (pinfunction "1_1") (pintype "passive"))
    )
    (net (code "111") (name "Net-(IC13-SENSE-)") (class "Default")
      (node (ref "C85") (pin "2") (pinfunction "2_2") (pintype "passive"))
      (node (ref "IC13") (pin "16") (pinfunction "SENSE-_16") (pintype "input"))
      (node (ref "R60") (pin "1") (pinfunction "1_1") (pintype "passive"))
    )
    (net (code "112") (name "Net-(IC13-SS)") (class "Default")
      (node (ref "C86") (pin "2") (pinfunction "2_2") (pintype "passive"))
      (node (ref "IC13") (pin "15") (pinfunction "SS_15") (pintype "input"))
    )
    (net (code "113") (name "Net-(IC13-SW)") (class "Default")
      (node (ref "C74") (pin "2") (pinfunction "2_2") (pintype "passive"))
      (node (ref "C78") (pin "1") (pinfunction "1_1") (pintype "passive"))
      (node (ref "D12") (pin "C") (pinfunction "C_C") (pintype "passive"))
      (node (ref "IC13") (pin "26") (pinfunction "SW_26") (pintype "output"))
      (node (ref "L4") (pin "1") (pinfunction "1_1") (pintype "passive"))
      (node (ref "Q7") (pin "3") (pinfunction "S_3") (pintype "passive"))
      (node (ref "Q8") (pin "2") (pinfunction "D_2") (pintype "passive"))
    )
    (net (code "114") (name "Net-(IC13-TG)") (class "Default")
      (node (ref "IC13") (pin "25") (pinfunction "TG_25") (pintype "output"))
      (node (ref "Q7") (pin "1") (pinfunction "G_1") (pintype "passive"))
    )
    (net (code "115") (name "Net-(IC13-VC)") (class "Default")
      (node (ref "C87") (pin "2") (pinfunction "2_2") (pintype "passive"))
      (node (ref "IC13") (pin "18") (pinfunction "VC_18") (pintype "passive"))
    )
    (net (code "116") (name "Net-(IC13-VIN)") (class "Default")
      (node (ref "C70") (pin "1") (pinfunction "1_1") (pintype "passive"))
      (node (ref "D10") (pin "C") (pinfunction "C_C") (pintype "passive"))
      (node (ref "D8") (pin "C") (pinfunction "C_C") (pintype "passive"))
      (node (ref "IC13") (pin "3") (pinfunction "VIN_3") (pintype "passive"))
    )
    (net (code "117") (name "Net-(IC13-~{FAULT})") (class "Default")
      (node (ref "IC13") (pin "9") (pinfunction "~{FAULT}_9") (pintype "output"))
      (node (ref "R68") (pin "1") (pinfunction "1_1") (pintype "passive"))
    )
    (net (code "118") (name "Net-(L1A-1)") (class "Default")
      (node (ref "C1") (pin "2") (pinfunction "2_2") (pintype "passive"))
      (node (ref "L1") (pin "3") (pinfunction "1_3") (pintype "passive"))
      (node (ref "R1") (pin "2") (pinfunction "2_2") (pintype "passive"))
      (node (ref "X1") (pin "1") (pinfunction "1_1") (pintype "passive"))
    )
    (net (code "119") (name "Net-(L2-Pad2)") (class "Default")
      (node (ref "L2") (pin "2") (pinfunction "2_2") (pintype "passive"))
      (node (ref "R34") (pin "1") (pinfunction "1_1") (pintype "passive"))
    )
    (net (code "120") (name "Net-(L4-Pad2)") (class "Default")
      (node (ref "L4") (pin "2") (pinfunction "2_2") (pintype "passive"))
      (node (ref "R58") (pin "1") (pinfunction "1_1") (pintype "passive"))
    )
    (net (code "121") (name "Net-(LED1-AG)") (class "Default")
      (node (ref "LED1") (pin "GREEN") (pinfunction "AG_GREEN") (pintype "passive"))
      (node (ref "Q4") (pin "2") (pinfunction "S_2") (pintype "passive"))
    )
    (net (code "122") (name "Net-(LED1-AR)") (class "Default")
      (node (ref "LED1") (pin "RED") (pinfunction "AR_RED") (pintype "passive"))
      (node (ref "R49") (pin "1") (pinfunction "1_1") (pintype "passive"))
    )
    (net (code "123") (name "Net-(LED2-AG)") (class "Default")
      (node (ref "LED2") (pin "GREEN") (pinfunction "AG_GREEN") (pintype "passive"))
      (node (ref "Q9") (pin "2") (pinfunction "S_2") (pintype "passive"))
    )
    (net (code "124") (name "Net-(LED2-AR)") (class "Default")
      (node (ref "LED2") (pin "RED") (pinfunction "AR_RED") (pintype "passive"))
      (node (ref "R73") (pin "1") (pinfunction "1_1") (pintype "passive"))
    )
    (net (code "125") (name "Net-(Q1-D-Pad2)") (class "Default")
      (node (ref "Q1") (pin "2") (pinfunction "D_2") (pintype "passive"))
      (node (ref "Q1") (pin "4") (pinfunction "D_4") (pintype "passive"))
      (node (ref "R28") (pin "2") (pinfunction "2_2") (pintype "passive"))
    )
    (net (code "126") (name "Net-(Q1-G)") (class "Default")
      (node (ref "D4") (pin "C") (pinfunction "C_C") (pintype "passive"))
      (node (ref "Q1") (pin "1") (pinfunction "G_1") (pintype "passive"))
      (node (ref "R29") (pin "2") (pinfunction "2_2") (pintype "passive"))
      (node (ref "ZD2") (pin "C") (pinfunction "C_C") (pintype "passive"))
    )
    (net (code "127") (name "Net-(Q1-S)") (class "Default")
      (node (ref "D3") (pin "A") (pinfunction "A_A") (pintype "passive"))
      (node (ref "D4") (pin "A") (pinfunction "A_A") (pintype "passive"))
      (node (ref "Q1") (pin "3") (pinfunction "S_3") (pintype "passive"))
    )
    (net (code "128") (name "Net-(Q4-D)") (class "Default")
      (node (ref "Q4") (pin "3") (pinfunction "D_3") (pintype "passive"))
      (node (ref "Q5") (pin "3") (pinfunction "D_3") (pintype "passive"))
    )
    (net (code "129") (name "Net-(Q6-D-Pad2)") (class "Default")
      (node (ref "Q6") (pin "2") (pinfunction "D_2") (pintype "passive"))
      (node (ref "Q6") (pin "4") (pinfunction "D_4") (pintype "passive"))
      (node (ref "R52") (pin "2") (pinfunction "2_2") (pintype "passive"))
    )
    (net (code "130") (name "Net-(Q6-G)") (class "Default")
      (node (ref "D9") (pin "C") (pinfunction "C_C") (pintype "passive"))
      (node (ref "Q6") (pin "1") (pinfunction "G_1") (pintype "passive"))
      (node (ref "R53") (pin "2") (pinfunction "2_2") (pintype "passive"))
      (node (ref "ZD4") (pin "C") (pinfunction "C_C") (pintype "passive"))
    )
    (net (code "131") (name "Net-(Q6-S)") (class "Default")
      (node (ref "D8") (pin "A") (pinfunction "A_A") (pintype "passive"))
      (node (ref "D9") (pin "A") (pinfunction "A_A") (pintype "passive"))
      (node (ref "Q6") (pin "3") (pinfunction "S_3") (pintype "passive"))
    )
    (net (code "132") (name "Net-(Q10-D)") (class "Default")
      (node (ref "Q10") (pin "3") (pinfunction "D_3") (pintype "passive"))
      (node (ref "Q9") (pin "3") (pinfunction "D_3") (pintype "passive"))
    )
    (net (code "133") (name "Net-(R34-Pad1S)") (class "Default")
      (node (ref "R34") (pin "1S") (pinfunction "1S_1S") (pintype "passive"))
      (node (ref "R35") (pin "2") (pinfunction "2_2") (pintype "passive"))
    )
    (net (code "134") (name "Net-(R34-Pad2S)") (class "Default")
      (node (ref "R34") (pin "2S") (pinfunction "2S_2S") (pintype "passive"))
      (node (ref "R36") (pin "2") (pinfunction "2_2") (pintype "passive"))
    )
    (net (code "135") (name "Net-(R58-Pad1S)") (class "Default")
      (node (ref "R58") (pin "1S") (pinfunction "1S_1S") (pintype "passive"))
      (node (ref "R59") (pin "2") (pinfunction "2_2") (pintype "passive"))
    )
    (net (code "136") (name "Net-(R58-Pad2S)") (class "Default")
      (node (ref "R58") (pin "2S") (pinfunction "2S_2S") (pintype "passive"))
      (node (ref "R60") (pin "2") (pinfunction "2_2") (pintype "passive"))
    )
    (net (code "137") (name "Net-(X1B-1)") (class "Default")
      (node (ref "C1") (pin "1") (pinfunction "1_1") (pintype "passive"))
      (node (ref "L1") (pin "1") (pinfunction "1_1") (pintype "passive"))
      (node (ref "R1") (pin "1") (pinfunction "1_1") (pintype "passive"))
      (node (ref "X1") (pin "2") (pinfunction "1_2") (pintype "passive"))
    )
    (net (code "138") (name "Net-(X3A-S)") (class "Default")
      (node (ref "JP2") (pin "2") (pinfunction "2_2") (pintype "passive"))
      (node (ref "R19") (pin "2") (pinfunction "2_2") (pintype "passive"))
      (node (ref "X3") (pin "1") (pinfunction "S_1") (pintype "passive"))
    )
    (net (code "139") (name "OE#1") (class "Default")
      (node (ref "IC11") (pin "4") (pinfunction "EV/UVLO_4") (pintype "input"))
      (node (ref "OE#1") (pin "2") (pinfunction "2_2") (pintype "passive"))
      (node (ref "Q4") (pin "1") (pinfunction "G_1") (pintype "passive"))
      (node (ref "R76") (pin "1") (pinfunction "1_1") (pintype "passive"))
    )
    (net (code "140") (name "OE#2") (class "Default")
      (node (ref "IC13") (pin "4") (pinfunction "EV/UVLO_4") (pintype "input"))
      (node (ref "OE#2") (pin "2") (pinfunction "2_2") (pintype "passive"))
      (node (ref "Q9") (pin "1") (pinfunction "G_1") (pintype "passive"))
      (node (ref "R77") (pin "1") (pinfunction "1_1") (pintype "passive"))
    )
    (net (code "141") (name "OE_SYNC") (class "Default")
      (node (ref "IC8") (pin "36") (pinfunction "PF7_36") (pintype "bidirectional"))
      (node (ref "RN1") (pin "8") (pinfunction "2_8") (pintype "passive"))
    )
    (net (code "142") (name "PE") (class "Default")
      (node (ref "C2") (pin "2") (pinfunction "2_2") (pintype "passive"))
      (node (ref "C3") (pin "1") (pinfunction "1_1") (pintype "passive"))
      (node (ref "C56") (pin "1") (pinfunction "1_1") (pintype "passive"))
      (node (ref "C63") (pin "1") (pinfunction "1_1") (pintype "passive"))
      (node (ref "C76") (pin "1") (pinfunction "1_1") (pintype "passive"))
      (node (ref "C83") (pin "1") (pinfunction "1_1") (pintype "passive"))
      (node (ref "J1") (pin "1") (pinfunction "P$1_1") (pintype "bidirectional"))
      (node (ref "J1") (pin "2") (pinfunction "P$1_2") (pintype "bidirectional"))
    )
    (net (code "143") (name "PWRGOOD") (class "Default")
      (node (ref "IC2") (pin "6") (pinfunction "PWRGD_6") (pintype "output"))
      (node (ref "IC8") (pin "40") (pinfunction "PB4_40") (pintype "bidirectional"))
    )
    (net (code "144") (name "SCLK") (class "Default")
      (node (ref "IC8") (pin "28") (pinfunction "PD8_28") (pintype "bidirectional"))
      (node (ref "RN1") (pin "7") (pinfunction "2_7") (pintype "passive"))
    )
    (net (code "145") (name "SWCLK") (class "Default")
      (node (ref "IC8") (pin "37") (pinfunction "PA14_37") (pintype "bidirectional"))
      (node (ref "RN2") (pin "2") (pinfunction "1_2") (pintype "passive"))
    )
    (net (code "146") (name "SWDIO") (class "Default")
      (node (ref "IC8") (pin "34") (pinfunction "PA13_34") (pintype "bidirectional"))
      (node (ref "RN2") (pin "4") (pinfunction "1_4") (pintype "passive"))
    )
    (net (code "147") (name "SWO") (class "Default")
      (node (ref "IC8") (pin "39") (pinfunction "PB3_39") (pintype "bidirectional"))
      (node (ref "RN2") (pin "1") (pinfunction "1_1") (pintype "passive"))
    )
    (net (code "148") (name "TCK") (class "Default")
      (node (ref "IC7") (pin "5") (pinfunction "IO4_5") (pintype "bidirectional"))
      (node (ref "RN2") (pin "7") (pinfunction "2_7") (pintype "passive"))
      (node (ref "X3") (pin "2") (pinfunction "S_2") (pintype "passive"))
    )
    (net (code "149") (name "TEMP#1") (class "Default")
      (node (ref "C34") (pin "2") (pinfunction "2_2") (pintype "passive"))
      (node (ref "IC8") (pin "10") (pinfunction "PA0_10") (pintype "bidirectional"))
      (node (ref "NTC1") (pin "2") (pinfunction "P$2_2") (pintype "bidirectional"))
      (node (ref "R21") (pin "1") (pinfunction "1_1") (pintype "passive"))
    )
    (net (code "150") (name "TEMP#2") (class "Default")
      (node (ref "C35") (pin "2") (pinfunction "2_2") (pintype "passive"))
      (node (ref "IC8") (pin "14") (pinfunction "PA4_14") (pintype "bidirectional"))
      (node (ref "NTC2") (pin "2") (pinfunction "P$2_2") (pintype "bidirectional"))
      (node (ref "R22") (pin "1") (pinfunction "1_1") (pintype "passive"))
    )
    (net (code "151") (name "TMS") (class "Default")
      (node (ref "IC7") (pin "4") (pinfunction "IO3_4") (pintype "bidirectional"))
      (node (ref "RN2") (pin "5") (pinfunction "2_5") (pintype "passive"))
      (node (ref "X3") (pin "4") (pinfunction "S_4") (pintype "passive"))
    )
    (net (code "152") (name "UART_RX") (class "Default")
      (node (ref "IC3") (pin "12") (pinfunction "B3_12") (pintype "output"))
      (node (ref "IC8") (pin "31") (pinfunction "PA10_31") (pintype "bidirectional"))
    )
    (net (code "153") (name "UART_TX") (class "Default")
      (node (ref "IC3") (pin "11") (pinfunction "B4_11") (pintype "input"))
      (node (ref "IC8") (pin "30") (pinfunction "PA9_30") (pintype "bidirectional"))
      (node (ref "TX_PU") (pin "1") (pinfunction "1_1") (pintype "passive"))
    )
    (net (code "154") (name "U_MON#1") (class "Default")
      (node (ref "C41") (pin "2") (pinfunction "2_2") (pintype "passive"))
      (node (ref "IC8") (pin "18") (pinfunction "PB0_18") (pintype "bidirectional"))
      (node (ref "R24") (pin "1") (pinfunction "1_1") (pintype "passive"))
    )
    (net (code "155") (name "U_MON#2") (class "Default")
      (node (ref "C43") (pin "2") (pinfunction "2_2") (pintype "passive"))
      (node (ref "IC8") (pin "20") (pinfunction "PB2_20") (pintype "bidirectional"))
      (node (ref "R26") (pin "1") (pinfunction "1_1") (pintype "passive"))
    )
    (net (code "156") (name "U_MON1") (class "Default")
      (node (ref "R24") (pin "2") (pinfunction "2_2") (pintype "passive"))
      (node (ref "R40") (pin "1") (pinfunction "1_1") (pintype "passive"))
      (node (ref "R47") (pin "2") (pinfunction "2_2") (pintype "passive"))
    )
    (net (code "157") (name "U_MON2") (class "Default")
      (node (ref "R26") (pin "2") (pinfunction "2_2") (pintype "passive"))
      (node (ref "R64") (pin "1") (pinfunction "1_1") (pintype "passive"))
      (node (ref "R71") (pin "2") (pinfunction "2_2") (pintype "passive"))
    )
    (net (code "158") (name "U_SET#1") (class "Default")
      (node (ref "R48") (pin "1") (pinfunction "1_1") (pintype "passive"))
      (node (ref "U_SET1") (pin "1") (pinfunction "1_1") (pintype "passive"))
    )
    (net (code "159") (name "U_SET#2") (class "Default")
      (node (ref "R72") (pin "1") (pinfunction "1_1") (pintype "passive"))
      (node (ref "U_SET2") (pin "1") (pinfunction "1_1") (pintype "passive"))
    )
    (net (code "160") (name "U_SET_OUT#1") (class "Default")
      (node (ref "IC8") (pin "16") (pinfunction "PA6_16") (pintype "bidirectional"))
      (node (ref "U_SET1") (pin "2") (pinfunction "2_2") (pintype "passive"))
    )
    (net (code "161") (name "U_SET_OUT#2") (class "Default")
      (node (ref "IC8") (pin "15") (pinfunction "PA5_15") (pintype "bidirectional"))
      (node (ref "U_SET2") (pin "2") (pinfunction "2_2") (pintype "passive"))
    )
    (net (code "162") (name "V+") (class "Default")
      (node (ref "C17") (pin "1") (pinfunction "1_1") (pintype "passive"))
      (node (ref "C20") (pin "2") (pinfunction "2_2") (pintype "passive"))
      (node (ref "C7") (pin "1") (pinfunction "1_1") (pintype "passive"))
      (node (ref "IC1") (pin "1") (pinfunction "VDD1_1") (pintype "passive"))
      (node (ref "IC3") (pin "1") (pinfunction "VDD1_1") (pintype "passive"))
      (node (ref "IC4") (pin "8") (pinfunction "VCC_8") (pintype "power_in"))
      (node (ref "R11") (pin "1") (pinfunction "1_1") (pintype "passive"))
      (node (ref "R12") (pin "1") (pinfunction "1_1") (pintype "passive"))
      (node (ref "R13") (pin "1") (pinfunction "1_1") (pintype "passive"))
      (node (ref "X2") (pin "1") (pinfunction "1_1") (pintype "passive"))
    )
    (net (code "163") (name "VDDA") (class "Default")
      (node (ref "C37") (pin "2") (pinfunction "2_2") (pintype "passive"))
      (node (ref "C38") (pin "2") (pinfunction "2_2") (pintype "passive"))
      (node (ref "FB1") (pin "P$2") (pinfunction "2_P$2") (pintype "passive"))
      (node (ref "IC8") (pin "24") (pinfunction "VDDSD_24") (pintype "passive"))
    )
    (net (code "164") (name "VOUT1+") (class "Default")
      (node (ref "C59") (pin "1") (pinfunction "1_1") (pintype "passive"))
      (node (ref "C60") (pin "1") (pinfunction "1_1") (pintype "passive"))
      (node (ref "C62") (pin "+") (pinfunction "+_+") (pintype "passive"))
      (node (ref "L3") (pin "1") (pinfunction "1_1") (pintype "passive"))
      (node (ref "R34") (pin "2") (pinfunction "2_2") (pintype "passive"))
      (node (ref "R39") (pin "2") (pinfunction "2_2") (pintype "passive"))
      (node (ref "R40") (pin "2") (pinfunction "2_2") (pintype "passive"))
      (node (ref "ZD2") (pin "A") (pinfunction "A_A") (pintype "passive"))
    )
    (net (code "165") (name "VOUT2+") (class "Default")
      (node (ref "C79") (pin "1") (pinfunction "1_1") (pintype "passive"))
      (node (ref "C80") (pin "1") (pinfunction "1_1") (pintype "passive"))
      (node (ref "C82") (pin "+") (pinfunction "+_+") (pintype "passive"))
      (node (ref "L5") (pin "1") (pinfunction "1_1") (pintype "passive"))
      (node (ref "R58") (pin "2") (pinfunction "2_2") (pintype "passive"))
      (node (ref "R63") (pin "2") (pinfunction "2_2") (pintype "passive"))
      (node (ref "R64") (pin "2") (pinfunction "2_2") (pintype "passive"))
      (node (ref "ZD4") (pin "A") (pinfunction "A_A") (pintype "passive"))
    )
    (net (code "166") (name "VOUT_LC1+") (class "Default")
      (node (ref "C56") (pin "2") (pinfunction "2_2") (pintype "passive"))
      (node (ref "C57") (pin "1") (pinfunction "1_1") (pintype "passive"))
      (node (ref "C61") (pin "1") (pinfunction "+_1") (pintype "passive"))
      (node (ref "CH1") (pin "TIP") (pinfunction "TIP_TIP") (pintype "bidirectional"))
      (node (ref "J2") (pin "1") (pinfunction "1_1") (pintype "passive"))
      (node (ref "J2") (pin "1.1") (pinfunction "1_1.1") (pintype "passive"))
      (node (ref "L3") (pin "2") (pinfunction "2_2") (pintype "passive"))
      (node (ref "R41") (pin "1") (pinfunction "1_1") (pintype "passive"))
      (node (ref "ZD3") (pin "C") (pinfunction "C_C") (pintype "passive"))
    )
    (net (code "167") (name "VOUT_LC2+") (class "Default")
      (node (ref "C76") (pin "2") (pinfunction "2_2") (pintype "passive"))
      (node (ref "C77") (pin "1") (pinfunction "1_1") (pintype "passive"))
      (node (ref "C81") (pin "1") (pinfunction "+_1") (pintype "passive"))
      (node (ref "CH2") (pin "TIP") (pinfunction "TIP_TIP") (pintype "bidirectional"))
      (node (ref "J4") (pin "1") (pinfunction "1_1") (pintype "passive"))
      (node (ref "J4") (pin "1.1") (pinfunction "1_1.1") (pintype "passive"))
      (node (ref "L5") (pin "2") (pinfunction "2_2") (pintype "passive"))
      (node (ref "R65") (pin "1") (pinfunction "1_1") (pintype "passive"))
      (node (ref "ZD5") (pin "C") (pinfunction "C_C") (pintype "passive"))
    )
    (net (code "168") (name "VREF1") (class "Default")
      (node (ref "C53") (pin "1") (pinfunction "1_1") (pintype "passive"))
      (node (ref "IC11") (pin "10") (pinfunction "FBIN_10") (pintype "input"))
      (node (ref "IC11") (pin "13") (pinfunction "CTRL2_13") (pintype "input"))
      (node (ref "IC11") (pin "5") (pinfunction "VREF_5") (pintype "output"))
      (node (ref "R50") (pin "2") (pinfunction "2_2") (pintype "passive"))
    )
    (net (code "169") (name "VREF2") (class "Default")
      (node (ref "C73") (pin "1") (pinfunction "1_1") (pintype "passive"))
      (node (ref "IC13") (pin "10") (pinfunction "FBIN_10") (pintype "input"))
      (node (ref "IC13") (pin "13") (pinfunction "CTRL2_13") (pintype "input"))
      (node (ref "IC13") (pin "5") (pinfunction "VREF_5") (pintype "output"))
      (node (ref "R74") (pin "2") (pinfunction "2_2") (pintype "passive"))
    )
    (net (code "170") (name "unconnected-(IC8-PA2-Pad12)") (class "Default")
      (node (ref "IC8") (pin "12") (pinfunction "PA2_12") (pintype "bidirectional"))
    )
    (net (code "171") (name "unconnected-(IC8-PA3-Pad13)") (class "Default")
      (node (ref "IC8") (pin "13") (pinfunction "PA3_13") (pintype "bidirectional"))
    )
    (net (code "172") (name "unconnected-(IC8-PA8-Pad29)") (class "Default")
      (node (ref "IC8") (pin "29") (pinfunction "PA8_29") (pintype "bidirectional"))
    )
    (net (code "173") (name "unconnected-(IC8-PA15-Pad38)") (class "Default")
      (node (ref "IC8") (pin "38") (pinfunction "PA15_38") (pintype "bidirectional"))
    )
    (net (code "174") (name "unconnected-(IC8-PB7-Pad43)") (class "Default")
      (node (ref "IC8") (pin "43") (pinfunction "PB7_43") (pintype "bidirectional"))
    )
    (net (code "175") (name "unconnected-(IC8-PE9-Pad22)") (class "Default")
      (node (ref "IC8") (pin "22") (pinfunction "PE9_22") (pintype "bidirectional"))
    )
    (net (code "176") (name "unconnected-(IC8-PF6-Pad35)") (class "Default")
      (node (ref "IC8") (pin "35") (pinfunction "PF6_35") (pintype "bidirectional"))
    )
    (net (code "177") (name "unconnected-(IC8-VBAT-Pad1)") (class "Default")
      (node (ref "IC8") (pin "1") (pinfunction "VBAT_1") (pintype "passive"))
    )
    (net (code "178") (name "unconnected-(IC11-IVINMON-Pad8)") (class "Default")
      (node (ref "IC11") (pin "8") (pinfunction "IVINMON_8") (pintype "output"))
    )
    (net (code "179") (name "unconnected-(IC11-PWMOUT-Pad24)") (class "Default")
      (node (ref "IC11") (pin "24") (pinfunction "PWMOUT_24") (pintype "output"))
    )
    (net (code "180") (name "unconnected-(IC13-IVINMON-Pad8)") (class "Default")
      (node (ref "IC13") (pin "8") (pinfunction "IVINMON_8") (pintype "output"))
    )
    (net (code "181") (name "unconnected-(IC13-PWMOUT-Pad24)") (class "Default")
      (node (ref "IC13") (pin "24") (pinfunction "PWMOUT_24") (pintype "output"))
    )
    (net (code "182") (name "~{RESET}") (class "Default")
      (node (ref "IC1") (pin "15") (pinfunction "B1_15") (pintype "output"))
      (node (ref "JP3") (pin "1") (pinfunction "1_1") (pintype "passive"))
    )
  )
)
